# K104.net
KiCad netlist of a schematic drawn in EAGLE
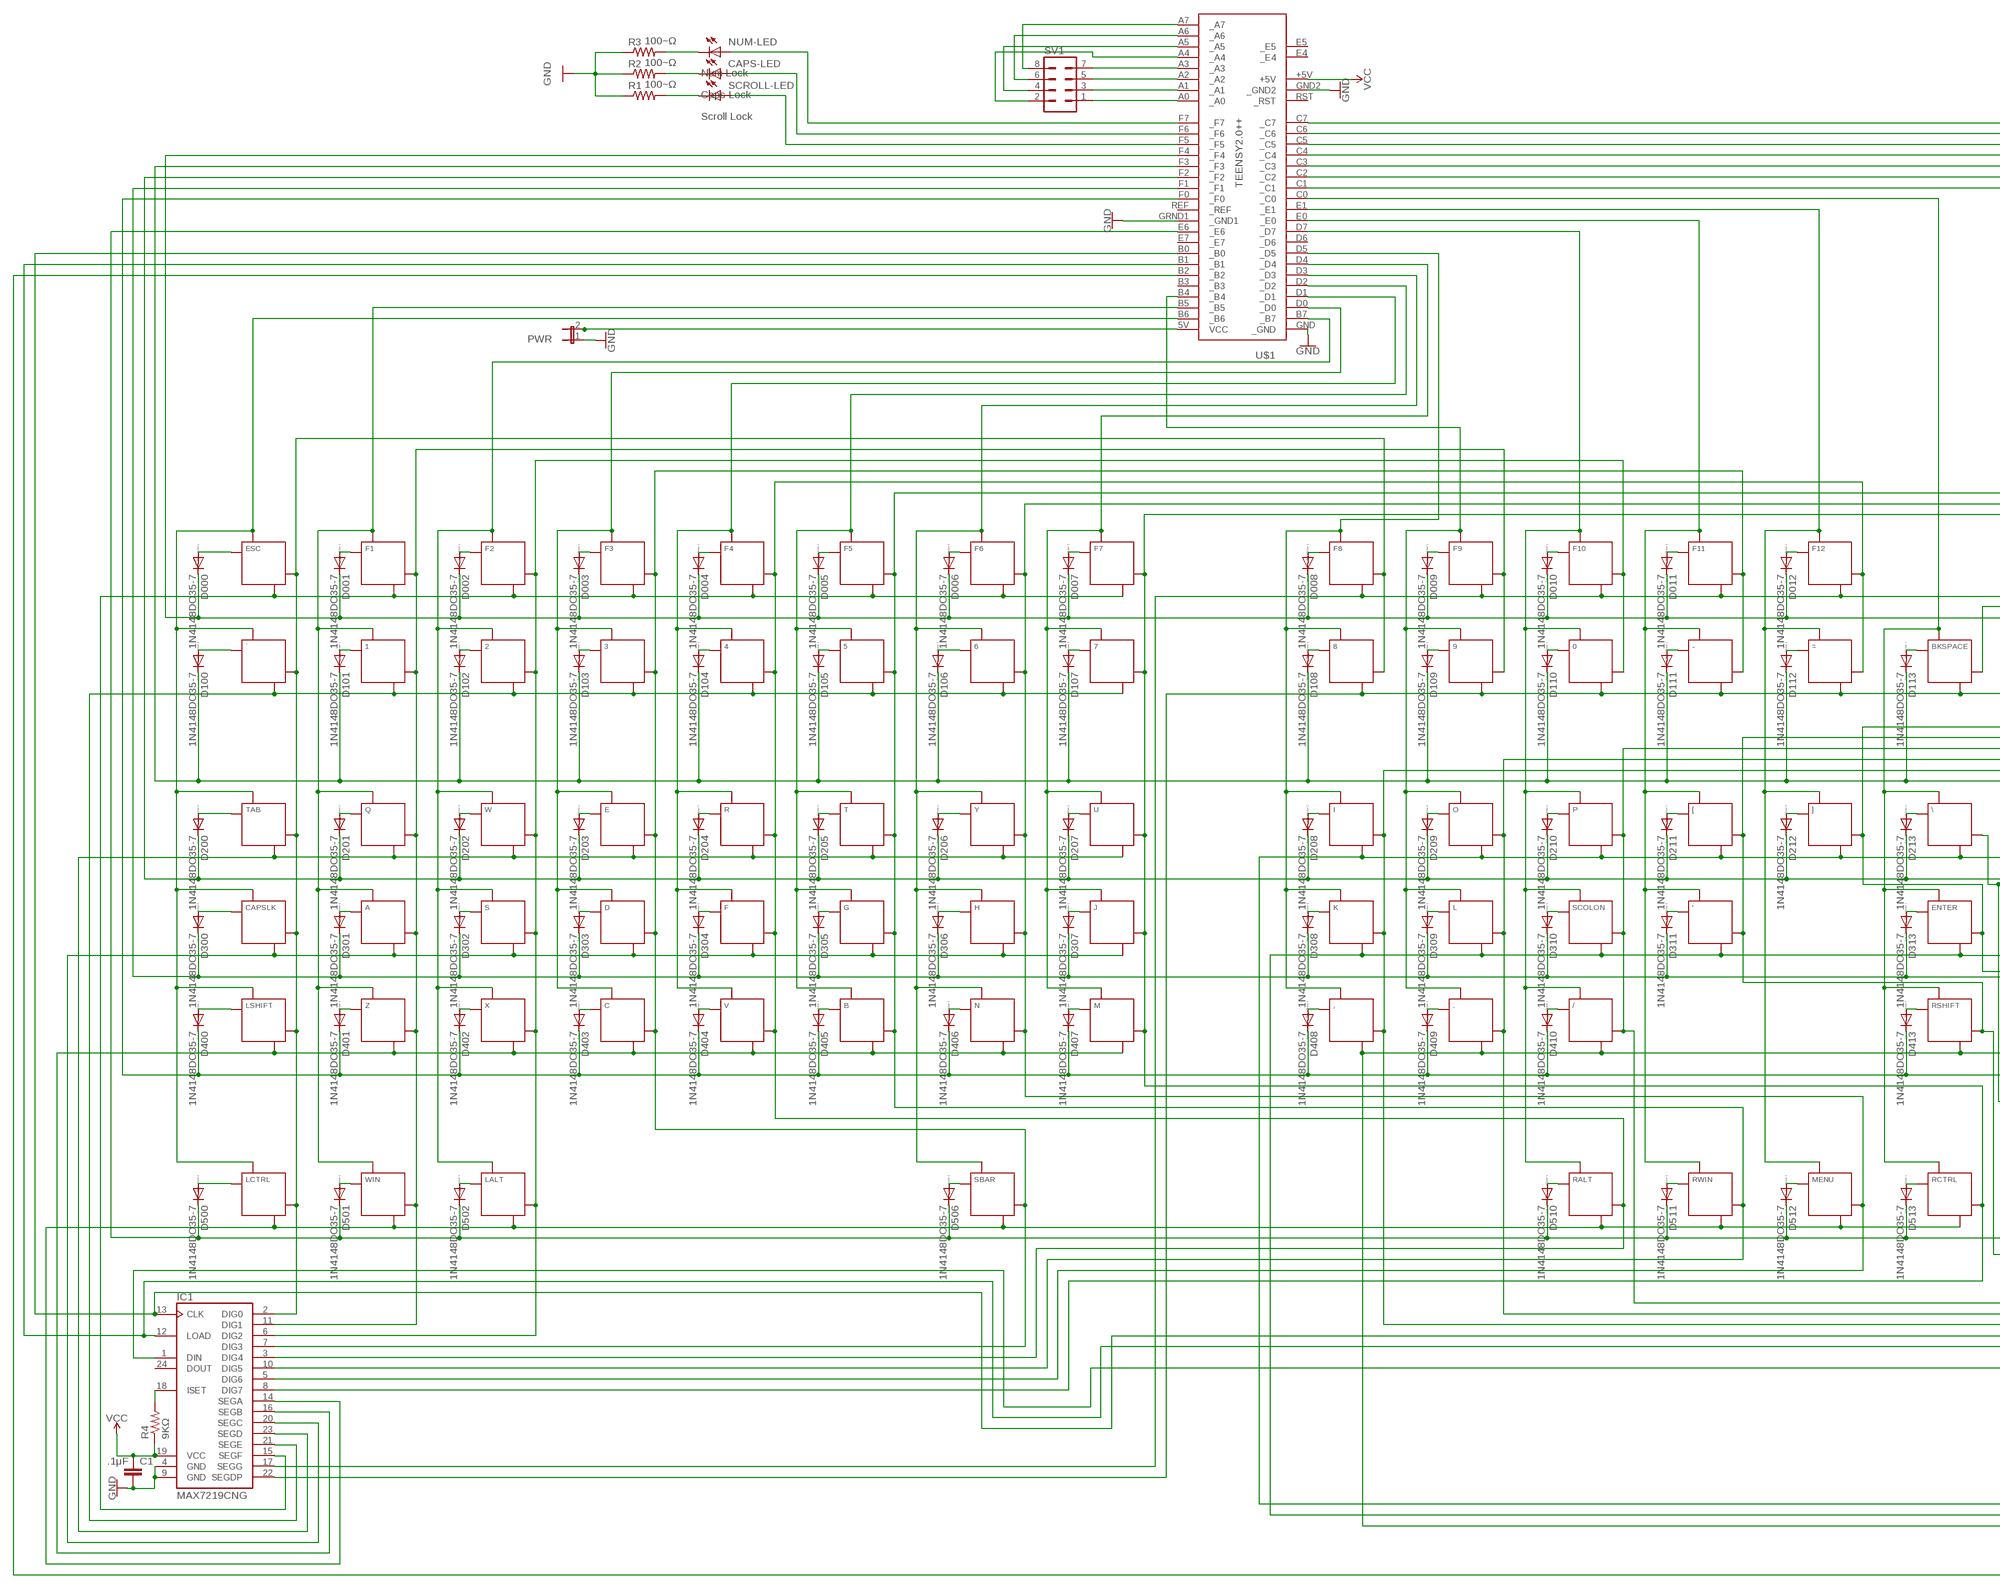
[diagram p0: schematic, sheet 1, part 1 of 2]
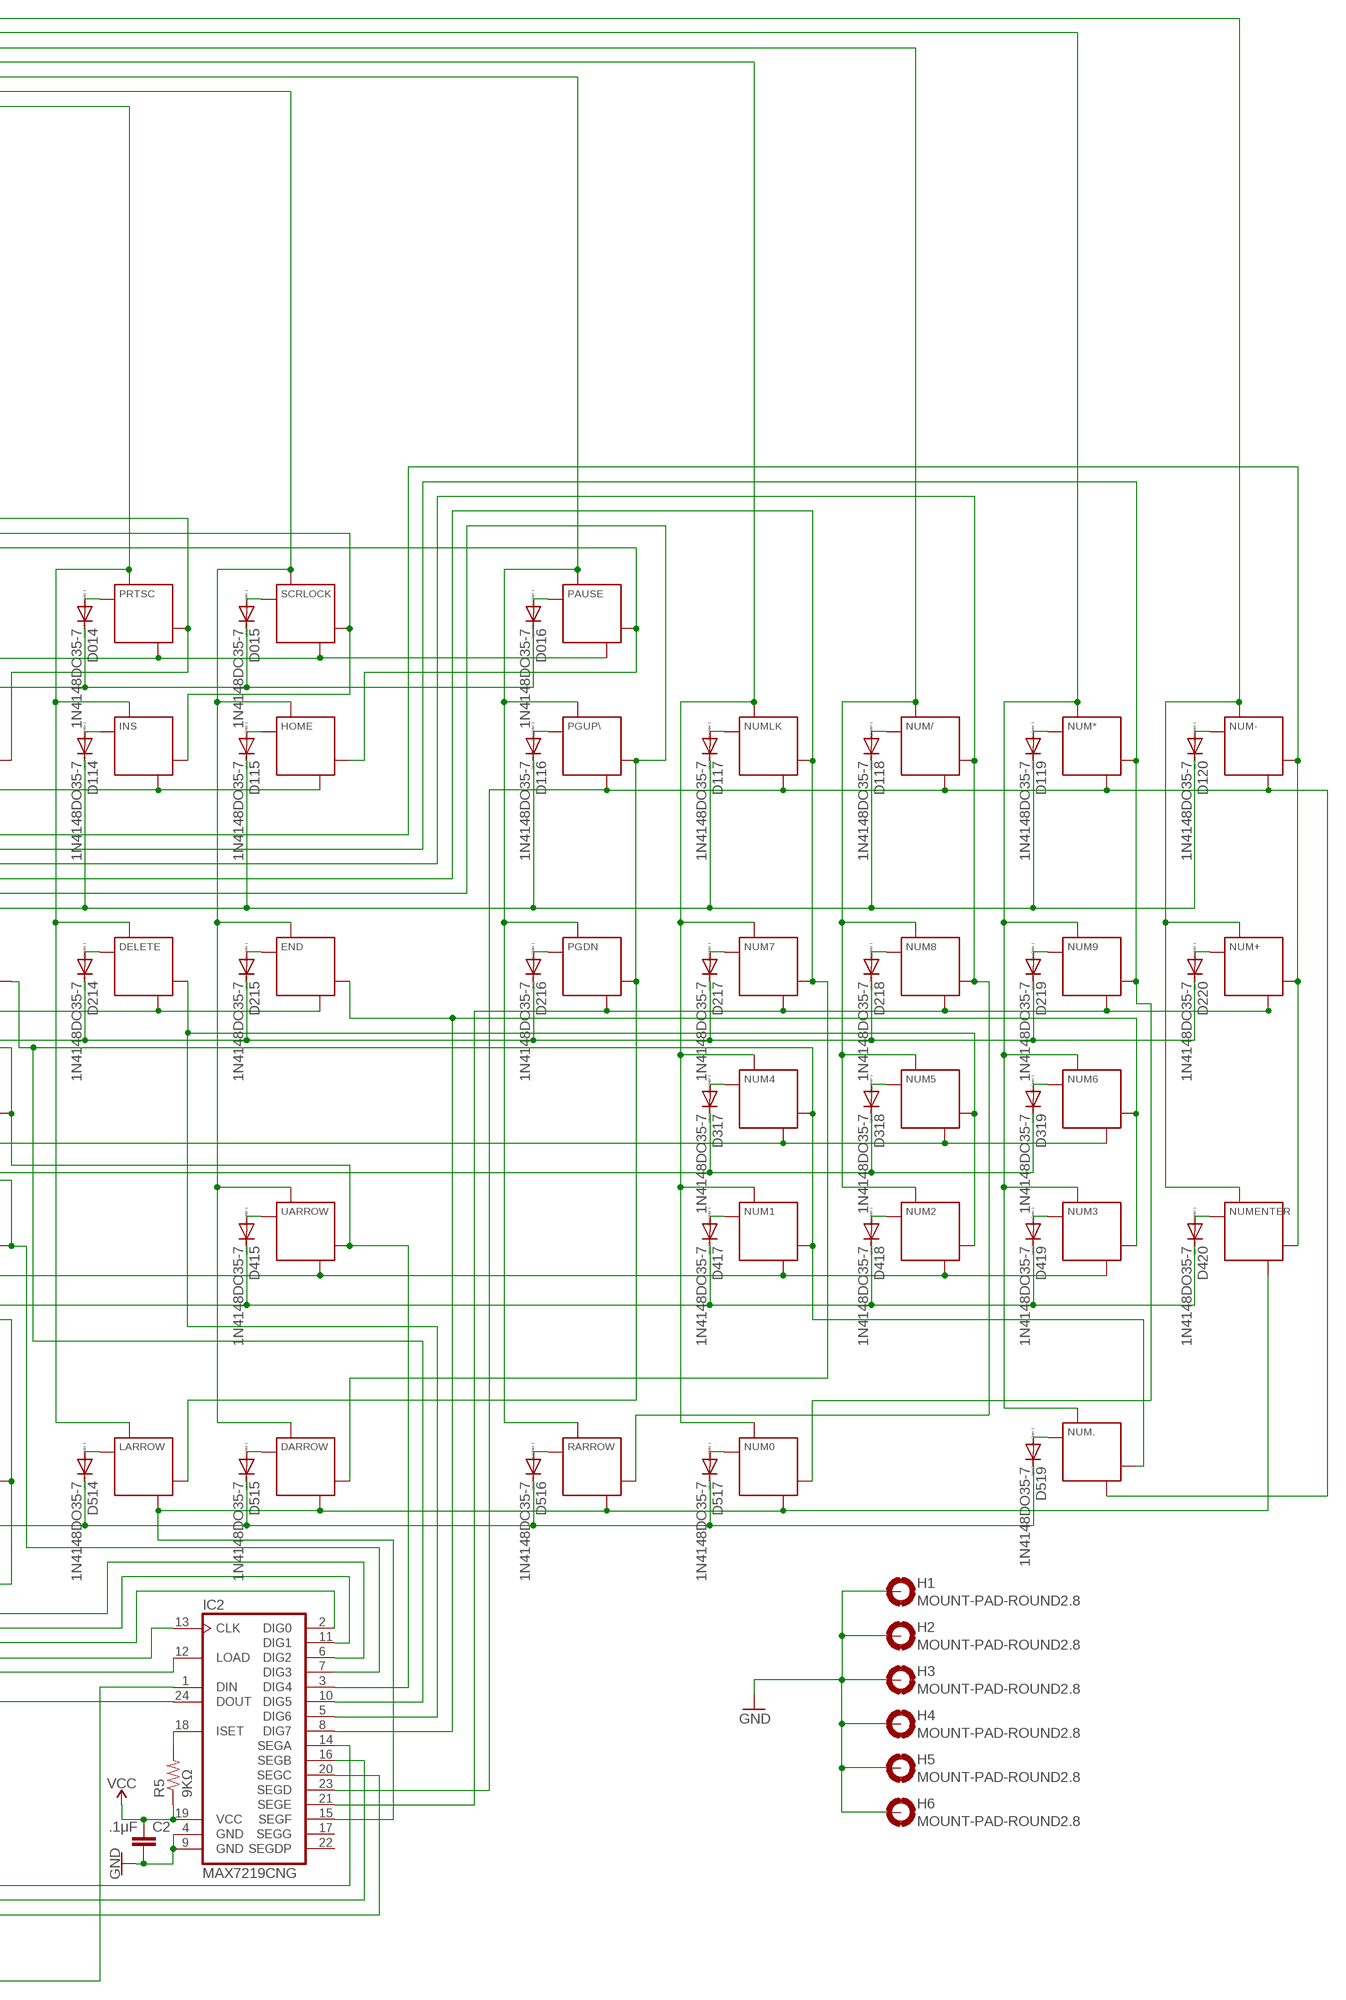
[diagram p1: schematic, sheet 1, part 2 of 2]

(export (version "E")
  (design (tool "Eeschema 10.0.6"))
  (components
    (comp (ref "'")
      (value "KEYSWITCH-LED-MX-1U-LED")
      (footprint "eagle-import:MX-1U-LED")
      (libsource (lib "eagle-import") (part "KEYSWITCH-LED-MX-1U-LED"))
    )
    (comp (ref ",")
      (value "KEYSWITCH-LED-MX-1U-LED")
      (footprint "eagle-import:MX-1U-LED")
      (libsource (lib "eagle-import") (part "KEYSWITCH-LED-MX-1U-LED"))
    )
    (comp (ref "-")
      (value "KEYSWITCH-LED-MX-1U-LED")
      (footprint "eagle-import:MX-1U-LED")
      (libsource (lib "eagle-import") (part "KEYSWITCH-LED-MX-1U-LED"))
    )
    (comp (ref ".")
      (value "KEYSWITCH-LED-MX-1U-LED")
      (footprint "eagle-import:MX-1U-LED")
      (libsource (lib "eagle-import") (part "KEYSWITCH-LED-MX-1U-LED"))
    )
    (comp (ref "/")
      (value "KEYSWITCH-LED-MX-1U-LED")
      (footprint "eagle-import:MX-1U-LED")
      (libsource (lib "eagle-import") (part "KEYSWITCH-LED-MX-1U-LED"))
    )
    (comp (ref "0")
      (value "KEYSWITCH-LED-MX-1U-LED")
      (footprint "eagle-import:MX-1U-LED")
      (libsource (lib "eagle-import") (part "KEYSWITCH-LED-MX-1U-LED"))
    )
    (comp (ref "1")
      (value "KEYSWITCH-LED-MX-1U-LED")
      (footprint "eagle-import:MX-1U-LED")
      (libsource (lib "eagle-import") (part "KEYSWITCH-LED-MX-1U-LED"))
    )
    (comp (ref "2")
      (value "KEYSWITCH-LED-MX-1U-LED")
      (footprint "eagle-import:MX-1U-LED")
      (libsource (lib "eagle-import") (part "KEYSWITCH-LED-MX-1U-LED"))
    )
    (comp (ref "3")
      (value "KEYSWITCH-LED-MX-1U-LED")
      (footprint "eagle-import:MX-1U-LED")
      (libsource (lib "eagle-import") (part "KEYSWITCH-LED-MX-1U-LED"))
    )
    (comp (ref "4")
      (value "KEYSWITCH-LED-MX-1U-LED")
      (footprint "eagle-import:MX-1U-LED")
      (libsource (lib "eagle-import") (part "KEYSWITCH-LED-MX-1U-LED"))
    )
    (comp (ref "5")
      (value "KEYSWITCH-LED-MX-1U-LED")
      (footprint "eagle-import:MX-1U-LED")
      (libsource (lib "eagle-import") (part "KEYSWITCH-LED-MX-1U-LED"))
    )
    (comp (ref "6")
      (value "KEYSWITCH-LED-MX-1U-LED")
      (footprint "eagle-import:MX-1U-LED")
      (libsource (lib "eagle-import") (part "KEYSWITCH-LED-MX-1U-LED"))
    )
    (comp (ref "7")
      (value "KEYSWITCH-LED-MX-1U-LED")
      (footprint "eagle-import:MX-1U-LED")
      (libsource (lib "eagle-import") (part "KEYSWITCH-LED-MX-1U-LED"))
    )
    (comp (ref "8")
      (value "KEYSWITCH-LED-MX-1U-LED")
      (footprint "eagle-import:MX-1U-LED")
      (libsource (lib "eagle-import") (part "KEYSWITCH-LED-MX-1U-LED"))
    )
    (comp (ref "9")
      (value "KEYSWITCH-LED-MX-1U-LED")
      (footprint "eagle-import:MX-1U-LED")
      (libsource (lib "eagle-import") (part "KEYSWITCH-LED-MX-1U-LED"))
    )
    (comp (ref "=")
      (value "KEYSWITCH-LED-MX-1U-LED")
      (footprint "eagle-import:MX-1U-LED")
      (libsource (lib "eagle-import") (part "KEYSWITCH-LED-MX-1U-LED"))
    )
    (comp (ref "A")
      (value "KEYSWITCH-LED-MX-1U-LED")
      (footprint "eagle-import:MX-1U-LED")
      (libsource (lib "eagle-import") (part "KEYSWITCH-LED-MX-1U-LED"))
    )
    (comp (ref "B")
      (value "KEYSWITCH-LED-MX-1U-LED")
      (footprint "eagle-import:MX-1U-LED")
      (libsource (lib "eagle-import") (part "KEYSWITCH-LED-MX-1U-LED"))
    )
    (comp (ref "BKSPACE")
      (value "KEYSWITCH-LED-MX-2U-LED")
      (footprint "eagle-import:MX-2U-LED")
      (libsource (lib "eagle-import") (part "KEYSWITCH-LED-MX-2U-LED"))
    )
    (comp (ref "C")
      (value "KEYSWITCH-LED-MX-1U-LED")
      (footprint "eagle-import:MX-1U-LED")
      (libsource (lib "eagle-import") (part "KEYSWITCH-LED-MX-1U-LED"))
    )
    (comp (ref "C1")
      (value ".1μF")
      (footprint "eagle-import:C025-024X044")
      (libsource (lib "eagle-import") (part "C-EU025-024X044"))
    )
    (comp (ref "C2")
      (value ".1μF")
      (footprint "eagle-import:C025-024X044")
      (libsource (lib "eagle-import") (part "C-EU025-024X044"))
    )
    (comp (ref "CAPS-LED")
      (value "Caps Lock")
      (footprint "eagle-import:LED3MM")
      (libsource (lib "eagle-import") (part "LED3MM"))
    )
    (comp (ref "CAPSLK")
      (value "KEYSWITCH-LED-MX-1U-LED")
      (footprint "eagle-import:MX-1U-LED")
      (libsource (lib "eagle-import") (part "KEYSWITCH-LED-MX-1U-LED"))
    )
    (comp (ref "D")
      (value "KEYSWITCH-LED-MX-1U-LED")
      (footprint "eagle-import:MX-1U-LED")
      (libsource (lib "eagle-import") (part "KEYSWITCH-LED-MX-1U-LED"))
    )
    (comp (ref "D000")
      (value "1N4148DO35-7")
      (footprint "eagle-import:DO35-7")
      (libsource (lib "eagle-import") (part "1N4148DO35-7"))
    )
    (comp (ref "D001")
      (value "1N4148DO35-7")
      (footprint "eagle-import:DO35-7")
      (libsource (lib "eagle-import") (part "1N4148DO35-7"))
    )
    (comp (ref "D002")
      (value "1N4148DO35-7")
      (footprint "eagle-import:DO35-7")
      (libsource (lib "eagle-import") (part "1N4148DO35-7"))
    )
    (comp (ref "D003")
      (value "1N4148DO35-7")
      (footprint "eagle-import:DO35-7")
      (libsource (lib "eagle-import") (part "1N4148DO35-7"))
    )
    (comp (ref "D004")
      (value "1N4148DO35-7")
      (footprint "eagle-import:DO35-7")
      (libsource (lib "eagle-import") (part "1N4148DO35-7"))
    )
    (comp (ref "D005")
      (value "1N4148DO35-7")
      (footprint "eagle-import:DO35-7")
      (libsource (lib "eagle-import") (part "1N4148DO35-7"))
    )
    (comp (ref "D006")
      (value "1N4148DO35-7")
      (footprint "eagle-import:DO35-7")
      (libsource (lib "eagle-import") (part "1N4148DO35-7"))
    )
    (comp (ref "D007")
      (value "1N4148DO35-7")
      (footprint "eagle-import:DO35-7")
      (libsource (lib "eagle-import") (part "1N4148DO35-7"))
    )
    (comp (ref "D008")
      (value "1N4148DO35-7")
      (footprint "eagle-import:DO35-7")
      (libsource (lib "eagle-import") (part "1N4148DO35-7"))
    )
    (comp (ref "D009")
      (value "1N4148DO35-7")
      (footprint "eagle-import:DO35-7")
      (libsource (lib "eagle-import") (part "1N4148DO35-7"))
    )
    (comp (ref "D010")
      (value "1N4148DO35-7")
      (footprint "eagle-import:DO35-7")
      (libsource (lib "eagle-import") (part "1N4148DO35-7"))
    )
    (comp (ref "D011")
      (value "1N4148DO35-7")
      (footprint "eagle-import:DO35-7")
      (libsource (lib "eagle-import") (part "1N4148DO35-7"))
    )
    (comp (ref "D012")
      (value "1N4148DO35-7")
      (footprint "eagle-import:DO35-7")
      (libsource (lib "eagle-import") (part "1N4148DO35-7"))
    )
    (comp (ref "D014")
      (value "1N4148DO35-7")
      (footprint "eagle-import:DO35-7")
      (libsource (lib "eagle-import") (part "1N4148DO35-7"))
    )
    (comp (ref "D015")
      (value "1N4148DO35-7")
      (footprint "eagle-import:DO35-7")
      (libsource (lib "eagle-import") (part "1N4148DO35-7"))
    )
    (comp (ref "D016")
      (value "1N4148DO35-7")
      (footprint "eagle-import:DO35-7")
      (libsource (lib "eagle-import") (part "1N4148DO35-7"))
    )
    (comp (ref "D100")
      (value "1N4148DO35-7")
      (footprint "eagle-import:DO35-7")
      (libsource (lib "eagle-import") (part "1N4148DO35-7"))
    )
    (comp (ref "D101")
      (value "1N4148DO35-7")
      (footprint "eagle-import:DO35-7")
      (libsource (lib "eagle-import") (part "1N4148DO35-7"))
    )
    (comp (ref "D102")
      (value "1N4148DO35-7")
      (footprint "eagle-import:DO35-7")
      (libsource (lib "eagle-import") (part "1N4148DO35-7"))
    )
    (comp (ref "D103")
      (value "1N4148DO35-7")
      (footprint "eagle-import:DO35-7")
      (libsource (lib "eagle-import") (part "1N4148DO35-7"))
    )
    (comp (ref "D104")
      (value "1N4148DO35-7")
      (footprint "eagle-import:DO35-7")
      (libsource (lib "eagle-import") (part "1N4148DO35-7"))
    )
    (comp (ref "D105")
      (value "1N4148DO35-7")
      (footprint "eagle-import:DO35-7")
      (libsource (lib "eagle-import") (part "1N4148DO35-7"))
    )
    (comp (ref "D106")
      (value "1N4148DO35-7")
      (footprint "eagle-import:DO35-7")
      (libsource (lib "eagle-import") (part "1N4148DO35-7"))
    )
    (comp (ref "D107")
      (value "1N4148DO35-7")
      (footprint "eagle-import:DO35-7")
      (libsource (lib "eagle-import") (part "1N4148DO35-7"))
    )
    (comp (ref "D108")
      (value "1N4148DO35-7")
      (footprint "eagle-import:DO35-7")
      (libsource (lib "eagle-import") (part "1N4148DO35-7"))
    )
    (comp (ref "D109")
      (value "1N4148DO35-7")
      (footprint "eagle-import:DO35-7")
      (libsource (lib "eagle-import") (part "1N4148DO35-7"))
    )
    (comp (ref "D110")
      (value "1N4148DO35-7")
      (footprint "eagle-import:DO35-7")
      (libsource (lib "eagle-import") (part "1N4148DO35-7"))
    )
    (comp (ref "D111")
      (value "1N4148DO35-7")
      (footprint "eagle-import:DO35-7")
      (libsource (lib "eagle-import") (part "1N4148DO35-7"))
    )
    (comp (ref "D112")
      (value "1N4148DO35-7")
      (footprint "eagle-import:DO35-7")
      (libsource (lib "eagle-import") (part "1N4148DO35-7"))
    )
    (comp (ref "D113")
      (value "1N4148DO35-7")
      (footprint "eagle-import:DO35-7")
      (libsource (lib "eagle-import") (part "1N4148DO35-7"))
    )
    (comp (ref "D114")
      (value "1N4148DO35-7")
      (footprint "eagle-import:DO35-7")
      (libsource (lib "eagle-import") (part "1N4148DO35-7"))
    )
    (comp (ref "D115")
      (value "1N4148DO35-7")
      (footprint "eagle-import:DO35-7")
      (libsource (lib "eagle-import") (part "1N4148DO35-7"))
    )
    (comp (ref "D116")
      (value "1N4148DO35-7")
      (footprint "eagle-import:DO35-7")
      (libsource (lib "eagle-import") (part "1N4148DO35-7"))
    )
    (comp (ref "D117")
      (value "1N4148DO35-7")
      (footprint "eagle-import:DO35-7")
      (libsource (lib "eagle-import") (part "1N4148DO35-7"))
    )
    (comp (ref "D118")
      (value "1N4148DO35-7")
      (footprint "eagle-import:DO35-7")
      (libsource (lib "eagle-import") (part "1N4148DO35-7"))
    )
    (comp (ref "D119")
      (value "1N4148DO35-7")
      (footprint "eagle-import:DO35-7")
      (libsource (lib "eagle-import") (part "1N4148DO35-7"))
    )
    (comp (ref "D120")
      (value "1N4148DO35-7")
      (footprint "eagle-import:DO35-7")
      (libsource (lib "eagle-import") (part "1N4148DO35-7"))
    )
    (comp (ref "D200")
      (value "1N4148DO35-7")
      (footprint "eagle-import:DO35-7")
      (libsource (lib "eagle-import") (part "1N4148DO35-7"))
    )
    (comp (ref "D201")
      (value "1N4148DO35-7")
      (footprint "eagle-import:DO35-7")
      (libsource (lib "eagle-import") (part "1N4148DO35-7"))
    )
    (comp (ref "D202")
      (value "1N4148DO35-7")
      (footprint "eagle-import:DO35-7")
      (libsource (lib "eagle-import") (part "1N4148DO35-7"))
    )
    (comp (ref "D203")
      (value "1N4148DO35-7")
      (footprint "eagle-import:DO35-7")
      (libsource (lib "eagle-import") (part "1N4148DO35-7"))
    )
    (comp (ref "D204")
      (value "1N4148DO35-7")
      (footprint "eagle-import:DO35-7")
      (libsource (lib "eagle-import") (part "1N4148DO35-7"))
    )
    (comp (ref "D205")
      (value "1N4148DO35-7")
      (footprint "eagle-import:DO35-7")
      (libsource (lib "eagle-import") (part "1N4148DO35-7"))
    )
    (comp (ref "D206")
      (value "1N4148DO35-7")
      (footprint "eagle-import:DO35-7")
      (libsource (lib "eagle-import") (part "1N4148DO35-7"))
    )
    (comp (ref "D207")
      (value "1N4148DO35-7")
      (footprint "eagle-import:DO35-7")
      (libsource (lib "eagle-import") (part "1N4148DO35-7"))
    )
    (comp (ref "D208")
      (value "1N4148DO35-7")
      (footprint "eagle-import:DO35-7")
      (libsource (lib "eagle-import") (part "1N4148DO35-7"))
    )
    (comp (ref "D209")
      (value "1N4148DO35-7")
      (footprint "eagle-import:DO35-7")
      (libsource (lib "eagle-import") (part "1N4148DO35-7"))
    )
    (comp (ref "D210")
      (value "1N4148DO35-7")
      (footprint "eagle-import:DO35-7")
      (libsource (lib "eagle-import") (part "1N4148DO35-7"))
    )
    (comp (ref "D211")
      (value "1N4148DO35-7")
      (footprint "eagle-import:DO35-7")
      (libsource (lib "eagle-import") (part "1N4148DO35-7"))
    )
    (comp (ref "D212")
      (value "1N4148DO35-7")
      (footprint "eagle-import:DO35-7")
      (libsource (lib "eagle-import") (part "1N4148DO35-7"))
    )
    (comp (ref "D213")
      (value "1N4148DO35-7")
      (footprint "eagle-import:DO35-7")
      (libsource (lib "eagle-import") (part "1N4148DO35-7"))
    )
    (comp (ref "D214")
      (value "1N4148DO35-7")
      (footprint "eagle-import:DO35-7")
      (libsource (lib "eagle-import") (part "1N4148DO35-7"))
    )
    (comp (ref "D215")
      (value "1N4148DO35-7")
      (footprint "eagle-import:DO35-7")
      (libsource (lib "eagle-import") (part "1N4148DO35-7"))
    )
    (comp (ref "D216")
      (value "1N4148DO35-7")
      (footprint "eagle-import:DO35-7")
      (libsource (lib "eagle-import") (part "1N4148DO35-7"))
    )
    (comp (ref "D217")
      (value "1N4148DO35-7")
      (footprint "eagle-import:DO35-7")
      (libsource (lib "eagle-import") (part "1N4148DO35-7"))
    )
    (comp (ref "D218")
      (value "1N4148DO35-7")
      (footprint "eagle-import:DO35-7")
      (libsource (lib "eagle-import") (part "1N4148DO35-7"))
    )
    (comp (ref "D219")
      (value "1N4148DO35-7")
      (footprint "eagle-import:DO35-7")
      (libsource (lib "eagle-import") (part "1N4148DO35-7"))
    )
    (comp (ref "D220")
      (value "1N4148DO35-7")
      (footprint "eagle-import:DO35-7")
      (libsource (lib "eagle-import") (part "1N4148DO35-7"))
    )
    (comp (ref "D300")
      (value "1N4148DO35-7")
      (footprint "eagle-import:DO35-7")
      (libsource (lib "eagle-import") (part "1N4148DO35-7"))
    )
    (comp (ref "D301")
      (value "1N4148DO35-7")
      (footprint "eagle-import:DO35-7")
      (libsource (lib "eagle-import") (part "1N4148DO35-7"))
    )
    (comp (ref "D302")
      (value "1N4148DO35-7")
      (footprint "eagle-import:DO35-7")
      (libsource (lib "eagle-import") (part "1N4148DO35-7"))
    )
    (comp (ref "D303")
      (value "1N4148DO35-7")
      (footprint "eagle-import:DO35-7")
      (libsource (lib "eagle-import") (part "1N4148DO35-7"))
    )
    (comp (ref "D304")
      (value "1N4148DO35-7")
      (footprint "eagle-import:DO35-7")
      (libsource (lib "eagle-import") (part "1N4148DO35-7"))
    )
    (comp (ref "D305")
      (value "1N4148DO35-7")
      (footprint "eagle-import:DO35-7")
      (libsource (lib "eagle-import") (part "1N4148DO35-7"))
    )
    (comp (ref "D306")
      (value "1N4148DO35-7")
      (footprint "eagle-import:DO35-7")
      (libsource (lib "eagle-import") (part "1N4148DO35-7"))
    )
    (comp (ref "D307")
      (value "1N4148DO35-7")
      (footprint "eagle-import:DO35-7")
      (libsource (lib "eagle-import") (part "1N4148DO35-7"))
    )
    (comp (ref "D308")
      (value "1N4148DO35-7")
      (footprint "eagle-import:DO35-7")
      (libsource (lib "eagle-import") (part "1N4148DO35-7"))
    )
    (comp (ref "D309")
      (value "1N4148DO35-7")
      (footprint "eagle-import:DO35-7")
      (libsource (lib "eagle-import") (part "1N4148DO35-7"))
    )
    (comp (ref "D310")
      (value "1N4148DO35-7")
      (footprint "eagle-import:DO35-7")
      (libsource (lib "eagle-import") (part "1N4148DO35-7"))
    )
    (comp (ref "D311")
      (value "1N4148DO35-7")
      (footprint "eagle-import:DO35-7")
      (libsource (lib "eagle-import") (part "1N4148DO35-7"))
    )
    (comp (ref "D313")
      (value "1N4148DO35-7")
      (footprint "eagle-import:DO35-7")
      (libsource (lib "eagle-import") (part "1N4148DO35-7"))
    )
    (comp (ref "D317")
      (value "1N4148DO35-7")
      (footprint "eagle-import:DO35-7")
      (libsource (lib "eagle-import") (part "1N4148DO35-7"))
    )
    (comp (ref "D318")
      (value "1N4148DO35-7")
      (footprint "eagle-import:DO35-7")
      (libsource (lib "eagle-import") (part "1N4148DO35-7"))
    )
    (comp (ref "D319")
      (value "1N4148DO35-7")
      (footprint "eagle-import:DO35-7")
      (libsource (lib "eagle-import") (part "1N4148DO35-7"))
    )
    (comp (ref "D400")
      (value "1N4148DO35-7")
      (footprint "eagle-import:DO35-7")
      (libsource (lib "eagle-import") (part "1N4148DO35-7"))
    )
    (comp (ref "D401")
      (value "1N4148DO35-7")
      (footprint "eagle-import:DO35-7")
      (libsource (lib "eagle-import") (part "1N4148DO35-7"))
    )
    (comp (ref "D402")
      (value "1N4148DO35-7")
      (footprint "eagle-import:DO35-7")
      (libsource (lib "eagle-import") (part "1N4148DO35-7"))
    )
    (comp (ref "D403")
      (value "1N4148DO35-7")
      (footprint "eagle-import:DO35-7")
      (libsource (lib "eagle-import") (part "1N4148DO35-7"))
    )
    (comp (ref "D404")
      (value "1N4148DO35-7")
      (footprint "eagle-import:DO35-7")
      (libsource (lib "eagle-import") (part "1N4148DO35-7"))
    )
    (comp (ref "D405")
      (value "1N4148DO35-7")
      (footprint "eagle-import:DO35-7")
      (libsource (lib "eagle-import") (part "1N4148DO35-7"))
    )
    (comp (ref "D406")
      (value "1N4148DO35-7")
      (footprint "eagle-import:DO35-7")
      (libsource (lib "eagle-import") (part "1N4148DO35-7"))
    )
    (comp (ref "D407")
      (value "1N4148DO35-7")
      (footprint "eagle-import:DO35-7")
      (libsource (lib "eagle-import") (part "1N4148DO35-7"))
    )
    (comp (ref "D408")
      (value "1N4148DO35-7")
      (footprint "eagle-import:DO35-7")
      (libsource (lib "eagle-import") (part "1N4148DO35-7"))
    )
    (comp (ref "D409")
      (value "1N4148DO35-7")
      (footprint "eagle-import:DO35-7")
      (libsource (lib "eagle-import") (part "1N4148DO35-7"))
    )
    (comp (ref "D410")
      (value "1N4148DO35-7")
      (footprint "eagle-import:DO35-7")
      (libsource (lib "eagle-import") (part "1N4148DO35-7"))
    )
    (comp (ref "D413")
      (value "1N4148DO35-7")
      (footprint "eagle-import:DO35-7")
      (libsource (lib "eagle-import") (part "1N4148DO35-7"))
    )
    (comp (ref "D415")
      (value "1N4148DO35-7")
      (footprint "eagle-import:DO35-7")
      (libsource (lib "eagle-import") (part "1N4148DO35-7"))
    )
    (comp (ref "D417")
      (value "1N4148DO35-7")
      (footprint "eagle-import:DO35-7")
      (libsource (lib "eagle-import") (part "1N4148DO35-7"))
    )
    (comp (ref "D418")
      (value "1N4148DO35-7")
      (footprint "eagle-import:DO35-7")
      (libsource (lib "eagle-import") (part "1N4148DO35-7"))
    )
    (comp (ref "D419")
      (value "1N4148DO35-7")
      (footprint "eagle-import:DO35-7")
      (libsource (lib "eagle-import") (part "1N4148DO35-7"))
    )
    (comp (ref "D420")
      (value "1N4148DO35-7")
      (footprint "eagle-import:DO35-7")
      (libsource (lib "eagle-import") (part "1N4148DO35-7"))
    )
    (comp (ref "D500")
      (value "1N4148DO35-7")
      (footprint "eagle-import:DO35-7")
      (libsource (lib "eagle-import") (part "1N4148DO35-7"))
    )
    (comp (ref "D501")
      (value "1N4148DO35-7")
      (footprint "eagle-import:DO35-7")
      (libsource (lib "eagle-import") (part "1N4148DO35-7"))
    )
    (comp (ref "D502")
      (value "1N4148DO35-7")
      (footprint "eagle-import:DO35-7")
      (libsource (lib "eagle-import") (part "1N4148DO35-7"))
    )
    (comp (ref "D506")
      (value "1N4148DO35-7")
      (footprint "eagle-import:DO35-7")
      (libsource (lib "eagle-import") (part "1N4148DO35-7"))
    )
    (comp (ref "D510")
      (value "1N4148DO35-7")
      (footprint "eagle-import:DO35-7")
      (libsource (lib "eagle-import") (part "1N4148DO35-7"))
    )
    (comp (ref "D511")
      (value "1N4148DO35-7")
      (footprint "eagle-import:DO35-7")
      (libsource (lib "eagle-import") (part "1N4148DO35-7"))
    )
    (comp (ref "D512")
      (value "1N4148DO35-7")
      (footprint "eagle-import:DO35-7")
      (libsource (lib "eagle-import") (part "1N4148DO35-7"))
    )
    (comp (ref "D513")
      (value "1N4148DO35-7")
      (footprint "eagle-import:DO35-7")
      (libsource (lib "eagle-import") (part "1N4148DO35-7"))
    )
    (comp (ref "D514")
      (value "1N4148DO35-7")
      (footprint "eagle-import:DO35-7")
      (libsource (lib "eagle-import") (part "1N4148DO35-7"))
    )
    (comp (ref "D515")
      (value "1N4148DO35-7")
      (footprint "eagle-import:DO35-7")
      (libsource (lib "eagle-import") (part "1N4148DO35-7"))
    )
    (comp (ref "D516")
      (value "1N4148DO35-7")
      (footprint "eagle-import:DO35-7")
      (libsource (lib "eagle-import") (part "1N4148DO35-7"))
    )
    (comp (ref "D517")
      (value "1N4148DO35-7")
      (footprint "eagle-import:DO35-7")
      (libsource (lib "eagle-import") (part "1N4148DO35-7"))
    )
    (comp (ref "D519")
      (value "1N4148DO35-7")
      (footprint "eagle-import:DO35-7")
      (libsource (lib "eagle-import") (part "1N4148DO35-7"))
    )
    (comp (ref "DARROW")
      (value "KEYSWITCH-LED-MX-1U-LED")
      (footprint "eagle-import:MX-1U-LED")
      (libsource (lib "eagle-import") (part "KEYSWITCH-LED-MX-1U-LED"))
    )
    (comp (ref "DELETE")
      (value "KEYSWITCH-LED-MX-1U-LED")
      (footprint "eagle-import:MX-1U-LED")
      (libsource (lib "eagle-import") (part "KEYSWITCH-LED-MX-1U-LED"))
    )
    (comp (ref "E")
      (value "KEYSWITCH-LED-MX-1U-LED")
      (footprint "eagle-import:MX-1U-LED")
      (libsource (lib "eagle-import") (part "KEYSWITCH-LED-MX-1U-LED"))
    )
    (comp (ref "END")
      (value "KEYSWITCH-LED-MX-1U-LED")
      (footprint "eagle-import:MX-1U-LED")
      (libsource (lib "eagle-import") (part "KEYSWITCH-LED-MX-1U-LED"))
    )
    (comp (ref "ENTER")
      (value "KEYSWITCH-LED-MX-2U-LED")
      (footprint "eagle-import:MX-2U-LED")
      (libsource (lib "eagle-import") (part "KEYSWITCH-LED-MX-2U-LED"))
    )
    (comp (ref "ESC")
      (value "S001")
      (footprint "eagle-import:MX-1U-LED")
      (libsource (lib "eagle-import") (part "KEYSWITCH-LED-MX-1U-LED"))
    )
    (comp (ref "F")
      (value "KEYSWITCH-LED-MX-1U-LED")
      (footprint "eagle-import:MX-1U-LED")
      (libsource (lib "eagle-import") (part "KEYSWITCH-LED-MX-1U-LED"))
    )
    (comp (ref "F1")
      (value "KEYSWITCH-LED-MX-1U-LED")
      (footprint "eagle-import:MX-1U-LED")
      (libsource (lib "eagle-import") (part "KEYSWITCH-LED-MX-1U-LED"))
    )
    (comp (ref "F2")
      (value "KEYSWITCH-LED-MX-1U-LED")
      (footprint "eagle-import:MX-1U-LED")
      (libsource (lib "eagle-import") (part "KEYSWITCH-LED-MX-1U-LED"))
    )
    (comp (ref "F3")
      (value "KEYSWITCH-LED-MX-1U-LED")
      (footprint "eagle-import:MX-1U-LED")
      (libsource (lib "eagle-import") (part "KEYSWITCH-LED-MX-1U-LED"))
    )
    (comp (ref "F4")
      (value "KEYSWITCH-LED-MX-1U-LED")
      (footprint "eagle-import:MX-1U-LED")
      (libsource (lib "eagle-import") (part "KEYSWITCH-LED-MX-1U-LED"))
    )
    (comp (ref "F5")
      (value "KEYSWITCH-LED-MX-1U-LED")
      (footprint "eagle-import:MX-1U-LED")
      (libsource (lib "eagle-import") (part "KEYSWITCH-LED-MX-1U-LED"))
    )
    (comp (ref "F6")
      (value "KEYSWITCH-LED-MX-1U-LED")
      (footprint "eagle-import:MX-1U-LED")
      (libsource (lib "eagle-import") (part "KEYSWITCH-LED-MX-1U-LED"))
    )
    (comp (ref "F7")
      (value "KEYSWITCH-LED-MX-1U-LED")
      (footprint "eagle-import:MX-1U-LED")
      (libsource (lib "eagle-import") (part "KEYSWITCH-LED-MX-1U-LED"))
    )
    (comp (ref "F8")
      (value "KEYSWITCH-LED-MX-1U-LED")
      (footprint "eagle-import:MX-1U-LED")
      (libsource (lib "eagle-import") (part "KEYSWITCH-LED-MX-1U-LED"))
    )
    (comp (ref "F9")
      (value "KEYSWITCH-LED-MX-1U-LED")
      (footprint "eagle-import:MX-1U-LED")
      (libsource (lib "eagle-import") (part "KEYSWITCH-LED-MX-1U-LED"))
    )
    (comp (ref "F10")
      (value "KEYSWITCH-LED-MX-1U-LED")
      (footprint "eagle-import:MX-1U-LED")
      (libsource (lib "eagle-import") (part "KEYSWITCH-LED-MX-1U-LED"))
    )
    (comp (ref "F11")
      (value "KEYSWITCH-LED-MX-1U-LED")
      (footprint "eagle-import:MX-1U-LED")
      (libsource (lib "eagle-import") (part "KEYSWITCH-LED-MX-1U-LED"))
    )
    (comp (ref "F12")
      (value "KEYSWITCH-LED-MX-1U-LED")
      (footprint "eagle-import:MX-1U-LED")
      (libsource (lib "eagle-import") (part "KEYSWITCH-LED-MX-1U-LED"))
    )
    (comp (ref "G")
      (value "KEYSWITCH-LED-MX-1U-LED")
      (footprint "eagle-import:MX-1U-LED")
      (libsource (lib "eagle-import") (part "KEYSWITCH-LED-MX-1U-LED"))
    )
    (comp (ref "H")
      (value "KEYSWITCH-LED-MX-1U-LED")
      (footprint "eagle-import:MX-1U-LED")
      (libsource (lib "eagle-import") (part "KEYSWITCH-LED-MX-1U-LED"))
    )
    (comp (ref "H1")
      (value "MOUNT-PAD-ROUND2.8")
      (footprint "eagle-import:2,8-PAD")
      (libsource (lib "eagle-import") (part "MOUNT-PAD-ROUND2.8"))
    )
    (comp (ref "H2")
      (value "MOUNT-PAD-ROUND2.8")
      (footprint "eagle-import:2,8-PAD")
      (libsource (lib "eagle-import") (part "MOUNT-PAD-ROUND2.8"))
    )
    (comp (ref "H3")
      (value "MOUNT-PAD-ROUND2.8")
      (footprint "eagle-import:2,8-PAD")
      (libsource (lib "eagle-import") (part "MOUNT-PAD-ROUND2.8"))
    )
    (comp (ref "H4")
      (value "MOUNT-PAD-ROUND2.8")
      (footprint "eagle-import:2,8-PAD")
      (libsource (lib "eagle-import") (part "MOUNT-PAD-ROUND2.8"))
    )
    (comp (ref "H5")
      (value "MOUNT-PAD-ROUND2.8")
      (footprint "eagle-import:2,8-PAD")
      (libsource (lib "eagle-import") (part "MOUNT-PAD-ROUND2.8"))
    )
    (comp (ref "H6")
      (value "MOUNT-PAD-ROUND2.8")
      (footprint "eagle-import:2,8-PAD")
      (libsource (lib "eagle-import") (part "MOUNT-PAD-ROUND2.8"))
    )
    (comp (ref "HOME")
      (value "KEYSWITCH-LED-MX-1U-LED")
      (footprint "eagle-import:MX-1U-LED")
      (libsource (lib "eagle-import") (part "KEYSWITCH-LED-MX-1U-LED"))
    )
    (comp (ref "I")
      (value "KEYSWITCH-LED-MX-1U-LED")
      (footprint "eagle-import:MX-1U-LED")
      (libsource (lib "eagle-import") (part "KEYSWITCH-LED-MX-1U-LED"))
    )
    (comp (ref "IC1")
      (value "MAX7219CNG")
      (footprint "eagle-import:DIL24-3")
      (fields (field (name "MF") "MAXIM"))
      (libsource (lib "eagle-import") (part "MAX7219CNG"))
    )
    (comp (ref "IC2")
      (value "MAX7219CNG")
      (footprint "eagle-import:DIL24-3")
      (fields (field (name "MF") "MAXIM"))
      (libsource (lib "eagle-import") (part "MAX7219CNG"))
    )
    (comp (ref "INS")
      (value "KEYSWITCH-LED-MX-1U-LED")
      (footprint "eagle-import:MX-1U-LED")
      (libsource (lib "eagle-import") (part "KEYSWITCH-LED-MX-1U-LED"))
    )
    (comp (ref "J")
      (value "KEYSWITCH-LED-MX-1U-LED")
      (footprint "eagle-import:MX-1U-LED")
      (libsource (lib "eagle-import") (part "KEYSWITCH-LED-MX-1U-LED"))
    )
    (comp (ref "K")
      (value "KEYSWITCH-LED-MX-1U-LED")
      (footprint "eagle-import:MX-1U-LED")
      (libsource (lib "eagle-import") (part "KEYSWITCH-LED-MX-1U-LED"))
    )
    (comp (ref "L")
      (value "KEYSWITCH-LED-MX-1U-LED")
      (footprint "eagle-import:MX-1U-LED")
      (libsource (lib "eagle-import") (part "KEYSWITCH-LED-MX-1U-LED"))
    )
    (comp (ref "LALT")
      (value "KEYSWITCH-LED-MX-1U-LED")
      (footprint "eagle-import:MX-1U-LED")
      (libsource (lib "eagle-import") (part "KEYSWITCH-LED-MX-1U-LED"))
    )
    (comp (ref "LARROW")
      (value "KEYSWITCH-LED-MX-1U-LED")
      (footprint "eagle-import:MX-1U-LED")
      (libsource (lib "eagle-import") (part "KEYSWITCH-LED-MX-1U-LED"))
    )
    (comp (ref "LCTRL")
      (value "KEYSWITCH-LED-MX-1U-LED")
      (footprint "eagle-import:MX-1U-LED")
      (libsource (lib "eagle-import") (part "KEYSWITCH-LED-MX-1U-LED"))
    )
    (comp (ref "LSHIFT")
      (value "KEYSWITCH-LED-MX-2U-LED")
      (footprint "eagle-import:MX-2U-LED")
      (libsource (lib "eagle-import") (part "KEYSWITCH-LED-MX-2U-LED"))
    )
    (comp (ref "M")
      (value "KEYSWITCH-LED-MX-1U-LED")
      (footprint "eagle-import:MX-1U-LED")
      (libsource (lib "eagle-import") (part "KEYSWITCH-LED-MX-1U-LED"))
    )
    (comp (ref "MENU")
      (value "KEYSWITCH-LED-MX-1U-LED")
      (footprint "eagle-import:MX-1U-LED")
      (libsource (lib "eagle-import") (part "KEYSWITCH-LED-MX-1U-LED"))
    )
    (comp (ref "N")
      (value "KEYSWITCH-LED-MX-1U-LED")
      (footprint "eagle-import:MX-1U-LED")
      (libsource (lib "eagle-import") (part "KEYSWITCH-LED-MX-1U-LED"))
    )
    (comp (ref "NUM*")
      (value "KEYSWITCH-LED-MX-1U-LED")
      (footprint "eagle-import:MX-1U-LED")
      (libsource (lib "eagle-import") (part "KEYSWITCH-LED-MX-1U-LED"))
    )
    (comp (ref "NUM+")
      (value "KEYSWITCH-LED-MX-2U-LED")
      (footprint "eagle-import:MX-2U-LED")
      (libsource (lib "eagle-import") (part "KEYSWITCH-LED-MX-2U-LED"))
    )
    (comp (ref "NUM-")
      (value "KEYSWITCH-LED-MX-1U-LED")
      (footprint "eagle-import:MX-1U-LED")
      (libsource (lib "eagle-import") (part "KEYSWITCH-LED-MX-1U-LED"))
    )
    (comp (ref "NUM-LED")
      (value "Num Lock")
      (footprint "eagle-import:LED3MM")
      (libsource (lib "eagle-import") (part "LED3MM"))
    )
    (comp (ref "NUM.")
      (value "KEYSWITCH-LED-MX-1U-LED")
      (footprint "eagle-import:MX-1U-LED")
      (libsource (lib "eagle-import") (part "KEYSWITCH-LED-MX-1U-LED"))
    )
    (comp (ref "NUM/")
      (value "KEYSWITCH-LED-MX-1U-LED")
      (footprint "eagle-import:MX-1U-LED")
      (libsource (lib "eagle-import") (part "KEYSWITCH-LED-MX-1U-LED"))
    )
    (comp (ref "NUM0")
      (value "KEYSWITCH-LED-MX-2U-LED")
      (footprint "eagle-import:MX-2U-LED")
      (libsource (lib "eagle-import") (part "KEYSWITCH-LED-MX-2U-LED"))
    )
    (comp (ref "NUM1")
      (value "KEYSWITCH-LED-MX-1U-LED")
      (footprint "eagle-import:MX-1U-LED")
      (libsource (lib "eagle-import") (part "KEYSWITCH-LED-MX-1U-LED"))
    )
    (comp (ref "NUM2")
      (value "KEYSWITCH-LED-MX-1U-LED")
      (footprint "eagle-import:MX-1U-LED")
      (libsource (lib "eagle-import") (part "KEYSWITCH-LED-MX-1U-LED"))
    )
    (comp (ref "NUM3")
      (value "KEYSWITCH-LED-MX-1U-LED")
      (footprint "eagle-import:MX-1U-LED")
      (libsource (lib "eagle-import") (part "KEYSWITCH-LED-MX-1U-LED"))
    )
    (comp (ref "NUM4")
      (value "KEYSWITCH-LED-MX-1U-LED")
      (footprint "eagle-import:MX-1U-LED")
      (libsource (lib "eagle-import") (part "KEYSWITCH-LED-MX-1U-LED"))
    )
    (comp (ref "NUM5")
      (value "KEYSWITCH-LED-MX-1U-LED")
      (footprint "eagle-import:MX-1U-LED")
      (libsource (lib "eagle-import") (part "KEYSWITCH-LED-MX-1U-LED"))
    )
    (comp (ref "NUM6")
      (value "KEYSWITCH-LED-MX-1U-LED")
      (footprint "eagle-import:MX-1U-LED")
      (libsource (lib "eagle-import") (part "KEYSWITCH-LED-MX-1U-LED"))
    )
    (comp (ref "NUM7")
      (value "KEYSWITCH-LED-MX-1U-LED")
      (footprint "eagle-import:MX-1U-LED")
      (libsource (lib "eagle-import") (part "KEYSWITCH-LED-MX-1U-LED"))
    )
    (comp (ref "NUM8")
      (value "KEYSWITCH-LED-MX-1U-LED")
      (footprint "eagle-import:MX-1U-LED")
      (libsource (lib "eagle-import") (part "KEYSWITCH-LED-MX-1U-LED"))
    )
    (comp (ref "NUM9")
      (value "KEYSWITCH-LED-MX-1U-LED")
      (footprint "eagle-import:MX-1U-LED")
      (libsource (lib "eagle-import") (part "KEYSWITCH-LED-MX-1U-LED"))
    )
    (comp (ref "NUMENTER")
      (value "KEYSWITCH-LED-MX-2U-LED")
      (footprint "eagle-import:MX-2U-LED")
      (libsource (lib "eagle-import") (part "KEYSWITCH-LED-MX-2U-LED"))
    )
    (comp (ref "NUMLK")
      (value "KEYSWITCH-LED-MX-1U-LED")
      (footprint "eagle-import:MX-1U-LED")
      (libsource (lib "eagle-import") (part "KEYSWITCH-LED-MX-1U-LED"))
    )
    (comp (ref "O")
      (value "KEYSWITCH-LED-MX-1U-LED")
      (footprint "eagle-import:MX-1U-LED")
      (libsource (lib "eagle-import") (part "KEYSWITCH-LED-MX-1U-LED"))
    )
    (comp (ref "P")
      (value "KEYSWITCH-LED-MX-1U-LED")
      (footprint "eagle-import:MX-1U-LED")
      (libsource (lib "eagle-import") (part "KEYSWITCH-LED-MX-1U-LED"))
    )
    (comp (ref "PAUSE")
      (value "KEYSWITCH-LED-MX-1U-LED")
      (footprint "eagle-import:MX-1U-LED")
      (libsource (lib "eagle-import") (part "KEYSWITCH-LED-MX-1U-LED"))
    )
    (comp (ref "PGDN")
      (value "KEYSWITCH-LED-MX-1U-LED")
      (footprint "eagle-import:MX-1U-LED")
      (libsource (lib "eagle-import") (part "KEYSWITCH-LED-MX-1U-LED"))
    )
    (comp (ref "PGUP\\")
      (value "KEYSWITCH-LED-MX-1U-LED")
      (footprint "eagle-import:MX-1U-LED")
      (libsource (lib "eagle-import") (part "KEYSWITCH-LED-MX-1U-LED"))
    )
    (comp (ref "PRTSC")
      (value "KEYSWITCH-LED-MX-1U-LED")
      (footprint "eagle-import:MX-1U-LED")
      (libsource (lib "eagle-import") (part "KEYSWITCH-LED-MX-1U-LED"))
    )
    (comp (ref "PWR")
      (value "JP1E")
      (footprint "eagle-import:JP1")
      (libsource (lib "eagle-import") (part "JP1E"))
    )
    (comp (ref "Q")
      (value "KEYSWITCH-LED-MX-1U-LED")
      (footprint "eagle-import:MX-1U-LED")
      (libsource (lib "eagle-import") (part "KEYSWITCH-LED-MX-1U-LED"))
    )
    (comp (ref "R")
      (value "KEYSWITCH-LED-MX-1U-LED")
      (footprint "eagle-import:MX-1U-LED")
      (libsource (lib "eagle-import") (part "KEYSWITCH-LED-MX-1U-LED"))
    )
    (comp (ref "R1")
      (value "100~Ω")
      (footprint "eagle-import:0204_7")
      (libsource (lib "eagle-import") (part "resistor_348_R-US_0204/7"))
    )
    (comp (ref "R2")
      (value "100~Ω")
      (footprint "eagle-import:0204_7")
      (libsource (lib "eagle-import") (part "resistor_348_R-US_0204/7"))
    )
    (comp (ref "R3")
      (value "100~Ω")
      (footprint "eagle-import:0204_7")
      (libsource (lib "eagle-import") (part "resistor_348_R-US_0204/7"))
    )
    (comp (ref "R4")
      (value "9KΩ")
      (footprint "eagle-import:0204_7")
      (libsource (lib "eagle-import") (part "R-US_0204/7"))
    )
    (comp (ref "R5")
      (value "9KΩ")
      (footprint "eagle-import:0204_7")
      (libsource (lib "eagle-import") (part "R-US_0204/7"))
    )
    (comp (ref "RALT")
      (value "KEYSWITCH-LED-MX-1U-LED")
      (footprint "eagle-import:MX-1U-LED")
      (libsource (lib "eagle-import") (part "KEYSWITCH-LED-MX-1U-LED"))
    )
    (comp (ref "RARROW")
      (value "KEYSWITCH-LED-MX-1U-LED")
      (footprint "eagle-import:MX-1U-LED")
      (libsource (lib "eagle-import") (part "KEYSWITCH-LED-MX-1U-LED"))
    )
    (comp (ref "RCTRL")
      (value "KEYSWITCH-LED-MX-1U-LED")
      (footprint "eagle-import:MX-1U-LED")
      (libsource (lib "eagle-import") (part "KEYSWITCH-LED-MX-1U-LED"))
    )
    (comp (ref "RSHIFT")
      (value "KEYSWITCH-LED-MX-2U-LED")
      (footprint "eagle-import:MX-2U-LED")
      (libsource (lib "eagle-import") (part "KEYSWITCH-LED-MX-2U-LED"))
    )
    (comp (ref "RWIN")
      (value "KEYSWITCH-LED-MX-1U-LED")
      (footprint "eagle-import:MX-1U-LED")
      (libsource (lib "eagle-import") (part "KEYSWITCH-LED-MX-1U-LED"))
    )
    (comp (ref "S")
      (value "KEYSWITCH-LED-MX-1U-LED")
      (footprint "eagle-import:MX-1U-LED")
      (libsource (lib "eagle-import") (part "KEYSWITCH-LED-MX-1U-LED"))
    )
    (comp (ref "SBAR")
      (value "KEYSWITCH-LED-MX-6.25U-LED")
      (footprint "eagle-import:MX-6.25U-LED")
      (libsource (lib "eagle-import") (part "KEYSWITCH-LED-MX-6.25U-LED"))
    )
    (comp (ref "SCOLON")
      (value "KEYSWITCH-LED-MX-1U-LED")
      (footprint "eagle-import:MX-1U-LED")
      (libsource (lib "eagle-import") (part "KEYSWITCH-LED-MX-1U-LED"))
    )
    (comp (ref "SCRLOCK")
      (value "KEYSWITCH-LED-MX-1U-LED")
      (footprint "eagle-import:MX-1U-LED")
      (libsource (lib "eagle-import") (part "KEYSWITCH-LED-MX-1U-LED"))
    )
    (comp (ref "SCROLL-LED")
      (value "Scroll Lock")
      (footprint "eagle-import:LED3MM")
      (libsource (lib "eagle-import") (part "LED3MM"))
    )
    (comp (ref "SV1")
      (value "MA04-2")
      (footprint "eagle-import:MA04-2")
      (libsource (lib "eagle-import") (part "MA04-2"))
    )
    (comp (ref "T")
      (value "KEYSWITCH-LED-MX-1U-LED")
      (footprint "eagle-import:MX-1U-LED")
      (libsource (lib "eagle-import") (part "KEYSWITCH-LED-MX-1U-LED"))
    )
    (comp (ref "TAB")
      (value "KEYSWITCH-LED-MX-1U-LED")
      (footprint "eagle-import:MX-1U-LED")
      (libsource (lib "eagle-import") (part "KEYSWITCH-LED-MX-1U-LED"))
    )
    (comp (ref "U")
      (value "KEYSWITCH-LED-MX-1U-LED")
      (footprint "eagle-import:MX-1U-LED")
      (libsource (lib "eagle-import") (part "KEYSWITCH-LED-MX-1U-LED"))
    )
    (comp (ref "U$1")
      (value "TEENSY2.0++")
      (footprint "eagle-import:TEENSY2.0++")
      (libsource (lib "eagle-import") (part "TEENSY2.0++"))
    )
    (comp (ref "UARROW")
      (value "KEYSWITCH-LED-MX-1U-LED")
      (footprint "eagle-import:MX-1U-LED")
      (libsource (lib "eagle-import") (part "KEYSWITCH-LED-MX-1U-LED"))
    )
    (comp (ref "V")
      (value "KEYSWITCH-LED-MX-1U-LED")
      (footprint "eagle-import:MX-1U-LED")
      (libsource (lib "eagle-import") (part "KEYSWITCH-LED-MX-1U-LED"))
    )
    (comp (ref "W")
      (value "KEYSWITCH-LED-MX-1U-LED")
      (footprint "eagle-import:MX-1U-LED")
      (libsource (lib "eagle-import") (part "KEYSWITCH-LED-MX-1U-LED"))
    )
    (comp (ref "WIN")
      (value "KEYSWITCH-LED-MX-1U-LED")
      (footprint "eagle-import:MX-1U-LED")
      (libsource (lib "eagle-import") (part "KEYSWITCH-LED-MX-1U-LED"))
    )
    (comp (ref "X")
      (value "KEYSWITCH-LED-MX-1U-LED")
      (footprint "eagle-import:MX-1U-LED")
      (libsource (lib "eagle-import") (part "KEYSWITCH-LED-MX-1U-LED"))
    )
    (comp (ref "Y")
      (value "KEYSWITCH-LED-MX-1U-LED")
      (footprint "eagle-import:MX-1U-LED")
      (libsource (lib "eagle-import") (part "KEYSWITCH-LED-MX-1U-LED"))
    )
    (comp (ref "Z")
      (value "KEYSWITCH-LED-MX-1U-LED")
      (footprint "eagle-import:MX-1U-LED")
      (libsource (lib "eagle-import") (part "KEYSWITCH-LED-MX-1U-LED"))
    )
    (comp (ref "[")
      (value "KEYSWITCH-LED-MX-1U-LED")
      (footprint "eagle-import:MX-1U-LED")
      (libsource (lib "eagle-import") (part "KEYSWITCH-LED-MX-1U-LED"))
    )
    (comp (ref "\\\\")
      (value "KEYSWITCH-LED-MX-1U-LED")
      (footprint "eagle-import:MX-1U-LED")
      (libsource (lib "eagle-import") (part "KEYSWITCH-LED-MX-1U-LED"))
    )
    (comp (ref "]")
      (value "KEYSWITCH-LED-MX-1U-LED")
      (footprint "eagle-import:MX-1U-LED")
      (libsource (lib "eagle-import") (part "KEYSWITCH-LED-MX-1U-LED"))
    )
    (comp (ref "`")
      (value "KEYSWITCH-LED-MX-1U-LED")
      (footprint "eagle-import:MX-1U-LED")
      (libsource (lib "eagle-import") (part "KEYSWITCH-LED-MX-1U-LED"))
    )
  )
  (nets
    (net (code "1") (name "GND") (class "Default")
      (node (ref "C1") (pin "2") (pinfunction "2_2") (pintype "passive"))
      (node (ref "C2") (pin "2") (pinfunction "2_2") (pintype "passive"))
      (node (ref "H1") (pin "B2,8") (pinfunction "MOUNT_B2,8") (pintype "passive"))
      (node (ref "H2") (pin "B2,8") (pinfunction "MOUNT_B2,8") (pintype "passive"))
      (node (ref "H3") (pin "B2,8") (pinfunction "MOUNT_B2,8") (pintype "passive"))
      (node (ref "H4") (pin "B2,8") (pinfunction "MOUNT_B2,8") (pintype "passive"))
      (node (ref "H5") (pin "B2,8") (pinfunction "MOUNT_B2,8") (pintype "passive"))
      (node (ref "H6") (pin "B2,8") (pinfunction "MOUNT_B2,8") (pintype "passive"))
      (node (ref "IC1") (pin "4") (pinfunction "GND_4") (pintype "power_in"))
      (node (ref "IC1") (pin "9") (pinfunction "GND_9") (pintype "power_in"))
      (node (ref "IC2") (pin "4") (pinfunction "GND_4") (pintype "power_in"))
      (node (ref "IC2") (pin "9") (pinfunction "GND_9") (pintype "power_in"))
      (node (ref "PWR") (pin "1") (pinfunction "1_1") (pintype "passive"))
      (node (ref "R1") (pin "1") (pinfunction "1_1") (pintype "passive"))
      (node (ref "R2") (pin "1") (pinfunction "1_1") (pintype "passive"))
      (node (ref "R3") (pin "1") (pinfunction "1_1") (pintype "passive"))
      (node (ref "U$1") (pin "GND") (pinfunction "_GND_GND") (pintype "power_in"))
      (node (ref "U$1") (pin "GND2") (pinfunction "_GND2_GND2") (pintype "power_in"))
      (node (ref "U$1") (pin "GRND1") (pinfunction "_GND1_GRND1") (pintype "power_in"))
    )
    (net (code "2") (name "Net-('-P0)") (class "Default")
      (node (ref "'") (pin "MX1") (pinfunction "P0_MX1") (pintype "bidirectional"))
      (node (ref "D311") (pin "A") (pinfunction "A_A") (pintype "passive"))
    )
    (net (code "3") (name "Net-('-P1)") (class "Default")
      (node (ref "'") (pin "MX2") (pinfunction "P1_MX2") (pintype "bidirectional"))
      (node (ref "-") (pin "MX2") (pinfunction "P1_MX2") (pintype "bidirectional"))
      (node (ref "F11") (pin "MX2") (pinfunction "P1_MX2") (pintype "bidirectional"))
      (node (ref "RWIN") (pin "MX2") (pinfunction "P1_MX2") (pintype "bidirectional"))
      (node (ref "U$1") (pin "E0") (pinfunction "_E0_E0") (pintype "bidirectional"))
      (node (ref "[") (pin "MX2") (pinfunction "P1_MX2") (pintype "bidirectional"))
    )
    (net (code "4") (name "Net-(,-P0)") (class "Default")
      (node (ref ",") (pin "MX1") (pinfunction "P0_MX1") (pintype "bidirectional"))
      (node (ref "D408") (pin "A") (pinfunction "A_A") (pintype "passive"))
    )
    (net (code "5") (name "Net-(,-P1)") (class "Default")
      (node (ref ",") (pin "MX2") (pinfunction "P1_MX2") (pintype "bidirectional"))
      (node (ref "8") (pin "MX2") (pinfunction "P1_MX2") (pintype "bidirectional"))
      (node (ref "F8") (pin "MX2") (pinfunction "P1_MX2") (pintype "bidirectional"))
      (node (ref "I") (pin "MX2") (pinfunction "P1_MX2") (pintype "bidirectional"))
      (node (ref "K") (pin "MX2") (pinfunction "P1_MX2") (pintype "bidirectional"))
      (node (ref "U$1") (pin "D5") (pinfunction "_D5_D5") (pintype "bidirectional"))
    )
    (net (code "6") (name "Net-(--P0)") (class "Default")
      (node (ref "-") (pin "MX1") (pinfunction "P0_MX1") (pintype "bidirectional"))
      (node (ref "D111") (pin "A") (pinfunction "A_A") (pintype "passive"))
    )
    (net (code "7") (name "Net-(.-P0)") (class "Default")
      (node (ref ".") (pin "MX1") (pinfunction "P0_MX1") (pintype "bidirectional"))
      (node (ref "D409") (pin "A") (pinfunction "A_A") (pintype "passive"))
    )
    (net (code "8") (name "Net-(.-P1)") (class "Default")
      (node (ref ".") (pin "MX2") (pinfunction "P1_MX2") (pintype "bidirectional"))
      (node (ref "9") (pin "MX2") (pinfunction "P1_MX2") (pintype "bidirectional"))
      (node (ref "F9") (pin "MX2") (pinfunction "P1_MX2") (pintype "bidirectional"))
      (node (ref "L") (pin "MX2") (pinfunction "P1_MX2") (pintype "bidirectional"))
      (node (ref "O") (pin "MX2") (pinfunction "P1_MX2") (pintype "bidirectional"))
      (node (ref "U$1") (pin "B4") (pinfunction "_B4_B4") (pintype "bidirectional"))
    )
    (net (code "9") (name "Net-(/-P0)") (class "Default")
      (node (ref "/") (pin "MX1") (pinfunction "P0_MX1") (pintype "bidirectional"))
      (node (ref "D410") (pin "A") (pinfunction "A_A") (pintype "passive"))
    )
    (net (code "10") (name "Net-(/-P1)") (class "Default")
      (node (ref "/") (pin "MX2") (pinfunction "P1_MX2") (pintype "bidirectional"))
      (node (ref "0") (pin "MX2") (pinfunction "P1_MX2") (pintype "bidirectional"))
      (node (ref "F10") (pin "MX2") (pinfunction "P1_MX2") (pintype "bidirectional"))
      (node (ref "P") (pin "MX2") (pinfunction "P1_MX2") (pintype "bidirectional"))
      (node (ref "RALT") (pin "MX2") (pinfunction "P1_MX2") (pintype "bidirectional"))
      (node (ref "SCOLON") (pin "MX2") (pinfunction "P1_MX2") (pintype "bidirectional"))
      (node (ref "U$1") (pin "D7") (pinfunction "_D7_D7") (pintype "bidirectional"))
    )
    (net (code "11") (name "Net-(0-P0)") (class "Default")
      (node (ref "0") (pin "MX1") (pinfunction "P0_MX1") (pintype "bidirectional"))
      (node (ref "D110") (pin "A") (pinfunction "A_A") (pintype "passive"))
    )
    (net (code "12") (name "Net-(1-P0)") (class "Default")
      (node (ref "1") (pin "MX1") (pinfunction "P0_MX1") (pintype "bidirectional"))
      (node (ref "D101") (pin "A") (pinfunction "A_A") (pintype "passive"))
    )
    (net (code "13") (name "Net-(1-P1)") (class "Default")
      (node (ref "1") (pin "MX2") (pinfunction "P1_MX2") (pintype "bidirectional"))
      (node (ref "A") (pin "MX2") (pinfunction "P1_MX2") (pintype "bidirectional"))
      (node (ref "F1") (pin "MX2") (pinfunction "P1_MX2") (pintype "bidirectional"))
      (node (ref "Q") (pin "MX2") (pinfunction "P1_MX2") (pintype "bidirectional"))
      (node (ref "U$1") (pin "B5") (pinfunction "_B5_B5") (pintype "bidirectional"))
      (node (ref "WIN") (pin "MX2") (pinfunction "P1_MX2") (pintype "bidirectional"))
      (node (ref "Z") (pin "MX2") (pinfunction "P1_MX2") (pintype "bidirectional"))
    )
    (net (code "14") (name "Net-(2-P0)") (class "Default")
      (node (ref "2") (pin "MX1") (pinfunction "P0_MX1") (pintype "bidirectional"))
      (node (ref "D102") (pin "A") (pinfunction "A_A") (pintype "passive"))
    )
    (net (code "15") (name "Net-(2-P1)") (class "Default")
      (node (ref "2") (pin "MX2") (pinfunction "P1_MX2") (pintype "bidirectional"))
      (node (ref "F2") (pin "MX2") (pinfunction "P1_MX2") (pintype "bidirectional"))
      (node (ref "LALT") (pin "MX2") (pinfunction "P1_MX2") (pintype "bidirectional"))
      (node (ref "S") (pin "MX2") (pinfunction "P1_MX2") (pintype "bidirectional"))
      (node (ref "U$1") (pin "B7") (pinfunction "_B7_B7") (pintype "bidirectional"))
      (node (ref "W") (pin "MX2") (pinfunction "P1_MX2") (pintype "bidirectional"))
      (node (ref "X") (pin "MX2") (pinfunction "P1_MX2") (pintype "bidirectional"))
    )
    (net (code "16") (name "Net-(3-P0)") (class "Default")
      (node (ref "3") (pin "MX1") (pinfunction "P0_MX1") (pintype "bidirectional"))
      (node (ref "D103") (pin "A") (pinfunction "A_A") (pintype "passive"))
    )
    (net (code "17") (name "Net-(3-P1)") (class "Default")
      (node (ref "3") (pin "MX2") (pinfunction "P1_MX2") (pintype "bidirectional"))
      (node (ref "C") (pin "MX2") (pinfunction "P1_MX2") (pintype "bidirectional"))
      (node (ref "D") (pin "MX2") (pinfunction "P1_MX2") (pintype "bidirectional"))
      (node (ref "E") (pin "MX2") (pinfunction "P1_MX2") (pintype "bidirectional"))
      (node (ref "F3") (pin "MX2") (pinfunction "P1_MX2") (pintype "bidirectional"))
      (node (ref "U$1") (pin "D0") (pinfunction "_D0_D0") (pintype "bidirectional"))
    )
    (net (code "18") (name "Net-(4-P0)") (class "Default")
      (node (ref "4") (pin "MX1") (pinfunction "P0_MX1") (pintype "bidirectional"))
      (node (ref "D104") (pin "A") (pinfunction "A_A") (pintype "passive"))
    )
    (net (code "19") (name "Net-(4-P1)") (class "Default")
      (node (ref "4") (pin "MX2") (pinfunction "P1_MX2") (pintype "bidirectional"))
      (node (ref "F") (pin "MX2") (pinfunction "P1_MX2") (pintype "bidirectional"))
      (node (ref "F4") (pin "MX2") (pinfunction "P1_MX2") (pintype "bidirectional"))
      (node (ref "R") (pin "MX2") (pinfunction "P1_MX2") (pintype "bidirectional"))
      (node (ref "U$1") (pin "D1") (pinfunction "_D1_D1") (pintype "bidirectional"))
      (node (ref "V") (pin "MX2") (pinfunction "P1_MX2") (pintype "bidirectional"))
    )
    (net (code "20") (name "Net-(5-P0)") (class "Default")
      (node (ref "5") (pin "MX1") (pinfunction "P0_MX1") (pintype "bidirectional"))
      (node (ref "D105") (pin "A") (pinfunction "A_A") (pintype "passive"))
    )
    (net (code "21") (name "Net-(5-P1)") (class "Default")
      (node (ref "5") (pin "MX2") (pinfunction "P1_MX2") (pintype "bidirectional"))
      (node (ref "B") (pin "MX2") (pinfunction "P1_MX2") (pintype "bidirectional"))
      (node (ref "F5") (pin "MX2") (pinfunction "P1_MX2") (pintype "bidirectional"))
      (node (ref "G") (pin "MX2") (pinfunction "P1_MX2") (pintype "bidirectional"))
      (node (ref "T") (pin "MX2") (pinfunction "P1_MX2") (pintype "bidirectional"))
      (node (ref "U$1") (pin "D2") (pinfunction "_D2_D2") (pintype "bidirectional"))
    )
    (net (code "22") (name "Net-(6-P0)") (class "Default")
      (node (ref "6") (pin "MX1") (pinfunction "P0_MX1") (pintype "bidirectional"))
      (node (ref "D106") (pin "A") (pinfunction "A_A") (pintype "passive"))
    )
    (net (code "23") (name "Net-(6-P1)") (class "Default")
      (node (ref "6") (pin "MX2") (pinfunction "P1_MX2") (pintype "bidirectional"))
      (node (ref "F6") (pin "MX2") (pinfunction "P1_MX2") (pintype "bidirectional"))
      (node (ref "H") (pin "MX2") (pinfunction "P1_MX2") (pintype "bidirectional"))
      (node (ref "N") (pin "MX2") (pinfunction "P1_MX2") (pintype "bidirectional"))
      (node (ref "SBAR") (pin "MX2") (pinfunction "P1_MX2") (pintype "bidirectional"))
      (node (ref "U$1") (pin "D3") (pinfunction "_D3_D3") (pintype "bidirectional"))
      (node (ref "Y") (pin "MX2") (pinfunction "P1_MX2") (pintype "bidirectional"))
    )
    (net (code "24") (name "Net-(7-P0)") (class "Default")
      (node (ref "7") (pin "MX1") (pinfunction "P0_MX1") (pintype "bidirectional"))
      (node (ref "D107") (pin "A") (pinfunction "A_A") (pintype "passive"))
    )
    (net (code "25") (name "Net-(7-P1)") (class "Default")
      (node (ref "7") (pin "MX2") (pinfunction "P1_MX2") (pintype "bidirectional"))
      (node (ref "F7") (pin "MX2") (pinfunction "P1_MX2") (pintype "bidirectional"))
      (node (ref "J") (pin "MX2") (pinfunction "P1_MX2") (pintype "bidirectional"))
      (node (ref "M") (pin "MX2") (pinfunction "P1_MX2") (pintype "bidirectional"))
      (node (ref "U") (pin "MX2") (pinfunction "P1_MX2") (pintype "bidirectional"))
      (node (ref "U$1") (pin "D4") (pinfunction "_D4_D4") (pintype "bidirectional"))
    )
    (net (code "26") (name "Net-(8-P0)") (class "Default")
      (node (ref "8") (pin "MX1") (pinfunction "P0_MX1") (pintype "bidirectional"))
      (node (ref "D108") (pin "A") (pinfunction "A_A") (pintype "passive"))
    )
    (net (code "27") (name "Net-(9-P0)") (class "Default")
      (node (ref "9") (pin "MX1") (pinfunction "P0_MX1") (pintype "bidirectional"))
      (node (ref "D109") (pin "A") (pinfunction "A_A") (pintype "passive"))
    )
    (net (code "28") (name "Net-(=-P0)") (class "Default")
      (node (ref "=") (pin "MX1") (pinfunction "P0_MX1") (pintype "bidirectional"))
      (node (ref "D112") (pin "A") (pinfunction "A_A") (pintype "passive"))
    )
    (net (code "29") (name "Net-(=-P1)") (class "Default")
      (node (ref "=") (pin "MX2") (pinfunction "P1_MX2") (pintype "bidirectional"))
      (node (ref "F12") (pin "MX2") (pinfunction "P1_MX2") (pintype "bidirectional"))
      (node (ref "MENU") (pin "MX2") (pinfunction "P1_MX2") (pintype "bidirectional"))
      (node (ref "U$1") (pin "E1") (pinfunction "_E1_E1") (pintype "bidirectional"))
      (node (ref "]") (pin "MX2") (pinfunction "P1_MX2") (pintype "bidirectional"))
    )
    (net (code "30") (name "Net-(A-P0)") (class "Default")
      (node (ref "A") (pin "MX1") (pinfunction "P0_MX1") (pintype "bidirectional"))
      (node (ref "D301") (pin "A") (pinfunction "A_A") (pintype "passive"))
    )
    (net (code "31") (name "Net-(B-P0)") (class "Default")
      (node (ref "B") (pin "MX1") (pinfunction "P0_MX1") (pintype "bidirectional"))
      (node (ref "D405") (pin "A") (pinfunction "A_A") (pintype "passive"))
    )
    (net (code "32") (name "Net-(BKSPACE-P0)") (class "Default")
      (node (ref "BKSPACE") (pin "MX1") (pinfunction "P0_MX1") (pintype "bidirectional"))
      (node (ref "D113") (pin "A") (pinfunction "A_A") (pintype "passive"))
    )
    (net (code "33") (name "Net-(BKSPACE-P1)") (class "Default")
      (node (ref "BKSPACE") (pin "MX2") (pinfunction "P1_MX2") (pintype "bidirectional"))
      (node (ref "ENTER") (pin "MX2") (pinfunction "P1_MX2") (pintype "bidirectional"))
      (node (ref "RCTRL") (pin "MX2") (pinfunction "P1_MX2") (pintype "bidirectional"))
      (node (ref "RSHIFT") (pin "MX2") (pinfunction "P1_MX2") (pintype "bidirectional"))
      (node (ref "U$1") (pin "C0") (pinfunction "_C0_C0") (pintype "bidirectional"))
      (node (ref "\\\\") (pin "MX2") (pinfunction "P1_MX2") (pintype "bidirectional"))
    )
    (net (code "34") (name "Net-(C-P0)") (class "Default")
      (node (ref "C") (pin "MX1") (pinfunction "P0_MX1") (pintype "bidirectional"))
      (node (ref "D403") (pin "A") (pinfunction "A_A") (pintype "passive"))
    )
    (net (code "35") (name "Net-(CAPS-LED-C)") (class "Default")
      (node (ref "CAPS-LED") (pin "K") (pinfunction "C_K") (pintype "passive"))
      (node (ref "R2") (pin "2") (pinfunction "2_2") (pintype "passive"))
    )
    (net (code "36") (name "Net-(CAPSLK-P0)") (class "Default")
      (node (ref "CAPSLK") (pin "MX1") (pinfunction "P0_MX1") (pintype "bidirectional"))
      (node (ref "D300") (pin "A") (pinfunction "A_A") (pintype "passive"))
    )
    (net (code "37") (name "Net-(CAPSLK-P1)") (class "Default")
      (node (ref "CAPSLK") (pin "MX2") (pinfunction "P1_MX2") (pintype "bidirectional"))
      (node (ref "ESC") (pin "MX2") (pinfunction "P1_MX2") (pintype "bidirectional"))
      (node (ref "LCTRL") (pin "MX2") (pinfunction "P1_MX2") (pintype "bidirectional"))
      (node (ref "LSHIFT") (pin "MX2") (pinfunction "P1_MX2") (pintype "bidirectional"))
      (node (ref "TAB") (pin "MX2") (pinfunction "P1_MX2") (pintype "bidirectional"))
      (node (ref "U$1") (pin "B6") (pinfunction "_B6_B6") (pintype "bidirectional"))
      (node (ref "`") (pin "MX2") (pinfunction "P1_MX2") (pintype "bidirectional"))
    )
    (net (code "38") (name "Net-(D-P0)") (class "Default")
      (node (ref "D") (pin "MX1") (pinfunction "P0_MX1") (pintype "bidirectional"))
      (node (ref "D303") (pin "A") (pinfunction "A_A") (pintype "passive"))
    )
    (net (code "39") (name "Net-(DARROW-P0)") (class "Default")
      (node (ref "D515") (pin "A") (pinfunction "A_A") (pintype "passive"))
      (node (ref "DARROW") (pin "MX1") (pinfunction "P0_MX1") (pintype "bidirectional"))
    )
    (net (code "40") (name "Net-(DARROW-P1)") (class "Default")
      (node (ref "DARROW") (pin "MX2") (pinfunction "P1_MX2") (pintype "bidirectional"))
      (node (ref "END") (pin "MX2") (pinfunction "P1_MX2") (pintype "bidirectional"))
      (node (ref "HOME") (pin "MX2") (pinfunction "P1_MX2") (pintype "bidirectional"))
      (node (ref "SCRLOCK") (pin "MX2") (pinfunction "P1_MX2") (pintype "bidirectional"))
      (node (ref "U$1") (pin "C2") (pinfunction "_C2_C2") (pintype "bidirectional"))
      (node (ref "UARROW") (pin "MX2") (pinfunction "P1_MX2") (pintype "bidirectional"))
    )
    (net (code "41") (name "Net-(DELETE-P0)") (class "Default")
      (node (ref "D214") (pin "A") (pinfunction "A_A") (pintype "passive"))
      (node (ref "DELETE") (pin "MX1") (pinfunction "P0_MX1") (pintype "bidirectional"))
    )
    (net (code "42") (name "Net-(DELETE-P1)") (class "Default")
      (node (ref "DELETE") (pin "MX2") (pinfunction "P1_MX2") (pintype "bidirectional"))
      (node (ref "INS") (pin "MX2") (pinfunction "P1_MX2") (pintype "bidirectional"))
      (node (ref "LARROW") (pin "MX2") (pinfunction "P1_MX2") (pintype "bidirectional"))
      (node (ref "PRTSC") (pin "MX2") (pinfunction "P1_MX2") (pintype "bidirectional"))
      (node (ref "U$1") (pin "C1") (pinfunction "_C1_C1") (pintype "bidirectional"))
    )
    (net (code "43") (name "Net-(E-P0)") (class "Default")
      (node (ref "D203") (pin "A") (pinfunction "A_A") (pintype "passive"))
      (node (ref "E") (pin "MX1") (pinfunction "P0_MX1") (pintype "bidirectional"))
    )
    (net (code "44") (name "Net-(END-P0)") (class "Default")
      (node (ref "D215") (pin "A") (pinfunction "A_A") (pintype "passive"))
      (node (ref "END") (pin "MX1") (pinfunction "P0_MX1") (pintype "bidirectional"))
    )
    (net (code "45") (name "Net-(ENTER-P0)") (class "Default")
      (node (ref "D313") (pin "A") (pinfunction "A_A") (pintype "passive"))
      (node (ref "ENTER") (pin "MX1") (pinfunction "P0_MX1") (pintype "bidirectional"))
    )
    (net (code "46") (name "Net-(ESC-P0)") (class "Default")
      (node (ref "D000") (pin "A") (pinfunction "A_A") (pintype "passive"))
      (node (ref "ESC") (pin "MX1") (pinfunction "P0_MX1") (pintype "bidirectional"))
    )
    (net (code "47") (name "Net-(F-P0)") (class "Default")
      (node (ref "D304") (pin "A") (pinfunction "A_A") (pintype "passive"))
      (node (ref "F") (pin "MX1") (pinfunction "P0_MX1") (pintype "bidirectional"))
    )
    (net (code "48") (name "Net-(F1-P0)") (class "Default")
      (node (ref "D001") (pin "A") (pinfunction "A_A") (pintype "passive"))
      (node (ref "F1") (pin "MX1") (pinfunction "P0_MX1") (pintype "bidirectional"))
    )
    (net (code "49") (name "Net-(F2-P0)") (class "Default")
      (node (ref "D002") (pin "A") (pinfunction "A_A") (pintype "passive"))
      (node (ref "F2") (pin "MX1") (pinfunction "P0_MX1") (pintype "bidirectional"))
    )
    (net (code "50") (name "Net-(F3-P0)") (class "Default")
      (node (ref "D003") (pin "A") (pinfunction "A_A") (pintype "passive"))
      (node (ref "F3") (pin "MX1") (pinfunction "P0_MX1") (pintype "bidirectional"))
    )
    (net (code "51") (name "Net-(F4-P0)") (class "Default")
      (node (ref "D004") (pin "A") (pinfunction "A_A") (pintype "passive"))
      (node (ref "F4") (pin "MX1") (pinfunction "P0_MX1") (pintype "bidirectional"))
    )
    (net (code "52") (name "Net-(F5-P0)") (class "Default")
      (node (ref "D005") (pin "A") (pinfunction "A_A") (pintype "passive"))
      (node (ref "F5") (pin "MX1") (pinfunction "P0_MX1") (pintype "bidirectional"))
    )
    (net (code "53") (name "Net-(F6-P0)") (class "Default")
      (node (ref "D006") (pin "A") (pinfunction "A_A") (pintype "passive"))
      (node (ref "F6") (pin "MX1") (pinfunction "P0_MX1") (pintype "bidirectional"))
    )
    (net (code "54") (name "Net-(F7-P0)") (class "Default")
      (node (ref "D007") (pin "A") (pinfunction "A_A") (pintype "passive"))
      (node (ref "F7") (pin "MX1") (pinfunction "P0_MX1") (pintype "bidirectional"))
    )
    (net (code "55") (name "Net-(F8-P0)") (class "Default")
      (node (ref "D008") (pin "A") (pinfunction "A_A") (pintype "passive"))
      (node (ref "F8") (pin "MX1") (pinfunction "P0_MX1") (pintype "bidirectional"))
    )
    (net (code "56") (name "Net-(F9-P0)") (class "Default")
      (node (ref "D009") (pin "A") (pinfunction "A_A") (pintype "passive"))
      (node (ref "F9") (pin "MX1") (pinfunction "P0_MX1") (pintype "bidirectional"))
    )
    (net (code "57") (name "Net-(F10-P0)") (class "Default")
      (node (ref "D010") (pin "A") (pinfunction "A_A") (pintype "passive"))
      (node (ref "F10") (pin "MX1") (pinfunction "P0_MX1") (pintype "bidirectional"))
    )
    (net (code "58") (name "Net-(F11-P0)") (class "Default")
      (node (ref "D011") (pin "A") (pinfunction "A_A") (pintype "passive"))
      (node (ref "F11") (pin "MX1") (pinfunction "P0_MX1") (pintype "bidirectional"))
    )
    (net (code "59") (name "Net-(F12-P0)") (class "Default")
      (node (ref "D012") (pin "A") (pinfunction "A_A") (pintype "passive"))
      (node (ref "F12") (pin "MX1") (pinfunction "P0_MX1") (pintype "bidirectional"))
    )
    (net (code "60") (name "Net-(G-P0)") (class "Default")
      (node (ref "D305") (pin "A") (pinfunction "A_A") (pintype "passive"))
      (node (ref "G") (pin "MX1") (pinfunction "P0_MX1") (pintype "bidirectional"))
    )
    (net (code "61") (name "Net-(H-P0)") (class "Default")
      (node (ref "D306") (pin "A") (pinfunction "A_A") (pintype "passive"))
      (node (ref "H") (pin "MX1") (pinfunction "P0_MX1") (pintype "bidirectional"))
    )
    (net (code "62") (name "Net-(HOME-P0)") (class "Default")
      (node (ref "D115") (pin "A") (pinfunction "A_A") (pintype "passive"))
      (node (ref "HOME") (pin "MX1") (pinfunction "P0_MX1") (pintype "bidirectional"))
    )
    (net (code "63") (name "Net-(I-P0)") (class "Default")
      (node (ref "D208") (pin "A") (pinfunction "A_A") (pintype "passive"))
      (node (ref "I") (pin "MX1") (pinfunction "P0_MX1") (pintype "bidirectional"))
    )
    (net (code "64") (name "Net-(IC1-CLK)") (class "Default")
      (node (ref "IC1") (pin "13") (pinfunction "CLK_13") (pintype "input"))
      (node (ref "IC2") (pin "13") (pinfunction "CLK_13") (pintype "input"))
      (node (ref "U$1") (pin "B0") (pinfunction "_B0_B0") (pintype "bidirectional"))
    )
    (net (code "65") (name "Net-(IC1-DIG0)") (class "Default")
      (node (ref "8") (pin "LED-") (pinfunction "LED-_LED-") (pintype "bidirectional"))
      (node (ref "CAPSLK") (pin "LED-") (pinfunction "LED-_LED-") (pintype "bidirectional"))
      (node (ref "ESC") (pin "LED-") (pinfunction "LED-_LED-") (pintype "bidirectional"))
      (node (ref "F8") (pin "LED-") (pinfunction "LED-_LED-") (pintype "bidirectional"))
      (node (ref "IC1") (pin "2") (pinfunction "DIG0_2") (pintype "output"))
      (node (ref "LCTRL") (pin "LED-") (pinfunction "LED-_LED-") (pintype "bidirectional"))
      (node (ref "LSHIFT") (pin "LED-") (pinfunction "LED-_LED-") (pintype "bidirectional"))
      (node (ref "TAB") (pin "LED-") (pinfunction "LED-_LED-") (pintype "bidirectional"))
      (node (ref "`") (pin "LED-") (pinfunction "LED-_LED-") (pintype "bidirectional"))
    )
    (net (code "66") (name "Net-(IC1-DIG1)") (class "Default")
      (node (ref "1") (pin "LED-") (pinfunction "LED-_LED-") (pintype "bidirectional"))
      (node (ref "9") (pin "LED-") (pinfunction "LED-_LED-") (pintype "bidirectional"))
      (node (ref "A") (pin "LED-") (pinfunction "LED-_LED-") (pintype "bidirectional"))
      (node (ref "F1") (pin "LED-") (pinfunction "LED-_LED-") (pintype "bidirectional"))
      (node (ref "F9") (pin "LED-") (pinfunction "LED-_LED-") (pintype "bidirectional"))
      (node (ref "IC1") (pin "11") (pinfunction "DIG1_11") (pintype "output"))
      (node (ref "Q") (pin "LED-") (pinfunction "LED-_LED-") (pintype "bidirectional"))
      (node (ref "WIN") (pin "LED-") (pinfunction "LED-_LED-") (pintype "bidirectional"))
      (node (ref "Z") (pin "LED-") (pinfunction "LED-_LED-") (pintype "bidirectional"))
    )
    (net (code "67") (name "Net-(IC1-DIG2)") (class "Default")
      (node (ref "0") (pin "LED-") (pinfunction "LED-_LED-") (pintype "bidirectional"))
      (node (ref "2") (pin "LED-") (pinfunction "LED-_LED-") (pintype "bidirectional"))
      (node (ref "F10") (pin "LED-") (pinfunction "LED-_LED-") (pintype "bidirectional"))
      (node (ref "F2") (pin "LED-") (pinfunction "LED-_LED-") (pintype "bidirectional"))
      (node (ref "IC1") (pin "6") (pinfunction "DIG2_6") (pintype "output"))
      (node (ref "LALT") (pin "LED-") (pinfunction "LED-_LED-") (pintype "bidirectional"))
      (node (ref "S") (pin "LED-") (pinfunction "LED-_LED-") (pintype "bidirectional"))
      (node (ref "W") (pin "LED-") (pinfunction "LED-_LED-") (pintype "bidirectional"))
      (node (ref "X") (pin "LED-") (pinfunction "LED-_LED-") (pintype "bidirectional"))
    )
    (net (code "68") (name "Net-(IC1-DIG3)") (class "Default")
      (node (ref "-") (pin "LED-") (pinfunction "LED-_LED-") (pintype "bidirectional"))
      (node (ref "3") (pin "LED-") (pinfunction "LED-_LED-") (pintype "bidirectional"))
      (node (ref "C") (pin "LED-") (pinfunction "LED-_LED-") (pintype "bidirectional"))
      (node (ref "D") (pin "LED-") (pinfunction "LED-_LED-") (pintype "bidirectional"))
      (node (ref "E") (pin "LED-") (pinfunction "LED-_LED-") (pintype "bidirectional"))
      (node (ref "F11") (pin "LED-") (pinfunction "LED-_LED-") (pintype "bidirectional"))
      (node (ref "F3") (pin "LED-") (pinfunction "LED-_LED-") (pintype "bidirectional"))
      (node (ref "IC1") (pin "7") (pinfunction "DIG3_7") (pintype "output"))
      (node (ref "SBAR") (pin "LED-") (pinfunction "LED-_LED-") (pintype "bidirectional"))
    )
    (net (code "69") (name "Net-(IC1-DIG4)") (class "Default")
      (node (ref "4") (pin "LED-") (pinfunction "LED-_LED-") (pintype "bidirectional"))
      (node (ref "=") (pin "LED-") (pinfunction "LED-_LED-") (pintype "bidirectional"))
      (node (ref "F") (pin "LED-") (pinfunction "LED-_LED-") (pintype "bidirectional"))
      (node (ref "F12") (pin "LED-") (pinfunction "LED-_LED-") (pintype "bidirectional"))
      (node (ref "F4") (pin "LED-") (pinfunction "LED-_LED-") (pintype "bidirectional"))
      (node (ref "IC1") (pin "3") (pinfunction "DIG4_3") (pintype "output"))
      (node (ref "R") (pin "LED-") (pinfunction "LED-_LED-") (pintype "bidirectional"))
      (node (ref "RALT") (pin "LED-") (pinfunction "LED-_LED-") (pintype "bidirectional"))
      (node (ref "V") (pin "LED-") (pinfunction "LED-_LED-") (pintype "bidirectional"))
    )
    (net (code "70") (name "Net-(IC1-DIG5)") (class "Default")
      (node (ref "5") (pin "LED-") (pinfunction "LED-_LED-") (pintype "bidirectional"))
      (node (ref "B") (pin "LED-") (pinfunction "LED-_LED-") (pintype "bidirectional"))
      (node (ref "BKSPACE") (pin "LED-") (pinfunction "LED-_LED-") (pintype "bidirectional"))
      (node (ref "F5") (pin "LED-") (pinfunction "LED-_LED-") (pintype "bidirectional"))
      (node (ref "G") (pin "LED-") (pinfunction "LED-_LED-") (pintype "bidirectional"))
      (node (ref "IC1") (pin "10") (pinfunction "DIG5_10") (pintype "output"))
      (node (ref "PRTSC") (pin "LED-") (pinfunction "LED-_LED-") (pintype "bidirectional"))
      (node (ref "RWIN") (pin "LED-") (pinfunction "LED-_LED-") (pintype "bidirectional"))
      (node (ref "T") (pin "LED-") (pinfunction "LED-_LED-") (pintype "bidirectional"))
    )
    (net (code "71") (name "Net-(IC1-DIG6)") (class "Default")
      (node (ref "6") (pin "LED-") (pinfunction "LED-_LED-") (pintype "bidirectional"))
      (node (ref "F6") (pin "LED-") (pinfunction "LED-_LED-") (pintype "bidirectional"))
      (node (ref "H") (pin "LED-") (pinfunction "LED-_LED-") (pintype "bidirectional"))
      (node (ref "IC1") (pin "5") (pinfunction "DIG6_5") (pintype "output"))
      (node (ref "INS") (pin "LED-") (pinfunction "LED-_LED-") (pintype "bidirectional"))
      (node (ref "MENU") (pin "LED-") (pinfunction "LED-_LED-") (pintype "bidirectional"))
      (node (ref "N") (pin "LED-") (pinfunction "LED-_LED-") (pintype "bidirectional"))
      (node (ref "SCRLOCK") (pin "LED-") (pinfunction "LED-_LED-") (pintype "bidirectional"))
      (node (ref "Y") (pin "LED-") (pinfunction "LED-_LED-") (pintype "bidirectional"))
    )
    (net (code "72") (name "Net-(IC1-DIG7)") (class "Default")
      (node (ref "7") (pin "LED-") (pinfunction "LED-_LED-") (pintype "bidirectional"))
      (node (ref "F7") (pin "LED-") (pinfunction "LED-_LED-") (pintype "bidirectional"))
      (node (ref "HOME") (pin "LED-") (pinfunction "LED-_LED-") (pintype "bidirectional"))
      (node (ref "IC1") (pin "8") (pinfunction "DIG7_8") (pintype "output"))
      (node (ref "J") (pin "LED-") (pinfunction "LED-_LED-") (pintype "bidirectional"))
      (node (ref "M") (pin "LED-") (pinfunction "LED-_LED-") (pintype "bidirectional"))
      (node (ref "PAUSE") (pin "LED-") (pinfunction "LED-_LED-") (pintype "bidirectional"))
      (node (ref "RCTRL") (pin "LED-") (pinfunction "LED-_LED-") (pintype "bidirectional"))
      (node (ref "U") (pin "LED-") (pinfunction "LED-_LED-") (pintype "bidirectional"))
    )
    (net (code "73") (name "Net-(IC1-DIN)") (class "Default")
      (node (ref "IC1") (pin "1") (pinfunction "DIN_1") (pintype "input"))
      (node (ref "IC2") (pin "24") (pinfunction "DOUT_24") (pintype "output"))
    )
    (net (code "74") (name "Net-(IC1-ISET)") (class "Default")
      (node (ref "IC1") (pin "18") (pinfunction "ISET_18") (pintype "input"))
      (node (ref "R4") (pin "2") (pinfunction "2_2") (pintype "passive"))
    )
    (net (code "75") (name "Net-(IC1-LOAD)") (class "Default")
      (node (ref "IC1") (pin "12") (pinfunction "LOAD_12") (pintype "input"))
      (node (ref "IC2") (pin "12") (pinfunction "LOAD_12") (pintype "input"))
      (node (ref "U$1") (pin "B1") (pinfunction "_B1_B1") (pintype "bidirectional"))
    )
    (net (code "76") (name "Net-(IC1-SEGA)") (class "Default")
      (node (ref "IC1") (pin "14") (pinfunction "SEGA_14") (pintype "output"))
      (node (ref "LALT") (pin "LED+") (pinfunction "LED+_LED+") (pintype "bidirectional"))
      (node (ref "LCTRL") (pin "LED+") (pinfunction "LED+_LED+") (pintype "bidirectional"))
      (node (ref "MENU") (pin "LED+") (pinfunction "LED+_LED+") (pintype "bidirectional"))
      (node (ref "RALT") (pin "LED+") (pinfunction "LED+_LED+") (pintype "bidirectional"))
      (node (ref "RCTRL") (pin "LED+") (pinfunction "LED+_LED+") (pintype "bidirectional"))
      (node (ref "RWIN") (pin "LED+") (pinfunction "LED+_LED+") (pintype "bidirectional"))
      (node (ref "SBAR") (pin "LED+") (pinfunction "LED+_LED+") (pintype "bidirectional"))
      (node (ref "WIN") (pin "LED+") (pinfunction "LED+_LED+") (pintype "bidirectional"))
    )
    (net (code "77") (name "Net-(IC1-SEGB)") (class "Default")
      (node (ref "B") (pin "LED+") (pinfunction "LED+_LED+") (pintype "bidirectional"))
      (node (ref "C") (pin "LED+") (pinfunction "LED+_LED+") (pintype "bidirectional"))
      (node (ref "IC1") (pin "16") (pinfunction "SEGB_16") (pintype "output"))
      (node (ref "LSHIFT") (pin "LED+") (pinfunction "LED+_LED+") (pintype "bidirectional"))
      (node (ref "M") (pin "LED+") (pinfunction "LED+_LED+") (pintype "bidirectional"))
      (node (ref "N") (pin "LED+") (pinfunction "LED+_LED+") (pintype "bidirectional"))
      (node (ref "V") (pin "LED+") (pinfunction "LED+_LED+") (pintype "bidirectional"))
      (node (ref "X") (pin "LED+") (pinfunction "LED+_LED+") (pintype "bidirectional"))
      (node (ref "Z") (pin "LED+") (pinfunction "LED+_LED+") (pintype "bidirectional"))
    )
    (net (code "78") (name "Net-(IC1-SEGC)") (class "Default")
      (node (ref "A") (pin "LED+") (pinfunction "LED+_LED+") (pintype "bidirectional"))
      (node (ref "CAPSLK") (pin "LED+") (pinfunction "LED+_LED+") (pintype "bidirectional"))
      (node (ref "D") (pin "LED+") (pinfunction "LED+_LED+") (pintype "bidirectional"))
      (node (ref "F") (pin "LED+") (pinfunction "LED+_LED+") (pintype "bidirectional"))
      (node (ref "G") (pin "LED+") (pinfunction "LED+_LED+") (pintype "bidirectional"))
      (node (ref "H") (pin "LED+") (pinfunction "LED+_LED+") (pintype "bidirectional"))
      (node (ref "IC1") (pin "20") (pinfunction "SEGC_20") (pintype "output"))
      (node (ref "J") (pin "LED+") (pinfunction "LED+_LED+") (pintype "bidirectional"))
      (node (ref "S") (pin "LED+") (pinfunction "LED+_LED+") (pintype "bidirectional"))
    )
    (net (code "79") (name "Net-(IC1-SEGD)") (class "Default")
      (node (ref "E") (pin "LED+") (pinfunction "LED+_LED+") (pintype "bidirectional"))
      (node (ref "IC1") (pin "23") (pinfunction "SEGD_23") (pintype "output"))
      (node (ref "Q") (pin "LED+") (pinfunction "LED+_LED+") (pintype "bidirectional"))
      (node (ref "R") (pin "LED+") (pinfunction "LED+_LED+") (pintype "bidirectional"))
      (node (ref "T") (pin "LED+") (pinfunction "LED+_LED+") (pintype "bidirectional"))
      (node (ref "TAB") (pin "LED+") (pinfunction "LED+_LED+") (pintype "bidirectional"))
      (node (ref "U") (pin "LED+") (pinfunction "LED+_LED+") (pintype "bidirectional"))
      (node (ref "W") (pin "LED+") (pinfunction "LED+_LED+") (pintype "bidirectional"))
      (node (ref "Y") (pin "LED+") (pinfunction "LED+_LED+") (pintype "bidirectional"))
    )
    (net (code "80") (name "Net-(IC1-SEGDP)") (class "Default")
      (node (ref "-") (pin "LED+") (pinfunction "LED+_LED+") (pintype "bidirectional"))
      (node (ref "0") (pin "LED+") (pinfunction "LED+_LED+") (pintype "bidirectional"))
      (node (ref "8") (pin "LED+") (pinfunction "LED+_LED+") (pintype "bidirectional"))
      (node (ref "9") (pin "LED+") (pinfunction "LED+_LED+") (pintype "bidirectional"))
      (node (ref "=") (pin "LED+") (pinfunction "LED+_LED+") (pintype "bidirectional"))
      (node (ref "BKSPACE") (pin "LED+") (pinfunction "LED+_LED+") (pintype "bidirectional"))
      (node (ref "HOME") (pin "LED+") (pinfunction "LED+_LED+") (pintype "bidirectional"))
      (node (ref "IC1") (pin "22") (pinfunction "SEGDP_22") (pintype "output"))
      (node (ref "INS") (pin "LED+") (pinfunction "LED+_LED+") (pintype "bidirectional"))
    )
    (net (code "81") (name "Net-(IC1-SEGE)") (class "Default")
      (node (ref "1") (pin "LED+") (pinfunction "LED+_LED+") (pintype "bidirectional"))
      (node (ref "2") (pin "LED+") (pinfunction "LED+_LED+") (pintype "bidirectional"))
      (node (ref "3") (pin "LED+") (pinfunction "LED+_LED+") (pintype "bidirectional"))
      (node (ref "4") (pin "LED+") (pinfunction "LED+_LED+") (pintype "bidirectional"))
      (node (ref "5") (pin "LED+") (pinfunction "LED+_LED+") (pintype "bidirectional"))
      (node (ref "6") (pin "LED+") (pinfunction "LED+_LED+") (pintype "bidirectional"))
      (node (ref "7") (pin "LED+") (pinfunction "LED+_LED+") (pintype "bidirectional"))
      (node (ref "IC1") (pin "21") (pinfunction "SEGE_21") (pintype "output"))
      (node (ref "`") (pin "LED+") (pinfunction "LED+_LED+") (pintype "bidirectional"))
    )
    (net (code "82") (name "Net-(IC1-SEGF)") (class "Default")
      (node (ref "ESC") (pin "LED+") (pinfunction "LED+_LED+") (pintype "bidirectional"))
      (node (ref "F1") (pin "LED+") (pinfunction "LED+_LED+") (pintype "bidirectional"))
      (node (ref "F2") (pin "LED+") (pinfunction "LED+_LED+") (pintype "bidirectional"))
      (node (ref "F3") (pin "LED+") (pinfunction "LED+_LED+") (pintype "bidirectional"))
      (node (ref "F4") (pin "LED+") (pinfunction "LED+_LED+") (pintype "bidirectional"))
      (node (ref "F5") (pin "LED+") (pinfunction "LED+_LED+") (pintype "bidirectional"))
      (node (ref "F6") (pin "LED+") (pinfunction "LED+_LED+") (pintype "bidirectional"))
      (node (ref "F7") (pin "LED+") (pinfunction "LED+_LED+") (pintype "bidirectional"))
      (node (ref "IC1") (pin "15") (pinfunction "SEGF_15") (pintype "output"))
    )
    (net (code "83") (name "Net-(IC1-SEGG)") (class "Default")
      (node (ref "F10") (pin "LED+") (pinfunction "LED+_LED+") (pintype "bidirectional"))
      (node (ref "F11") (pin "LED+") (pinfunction "LED+_LED+") (pintype "bidirectional"))
      (node (ref "F12") (pin "LED+") (pinfunction "LED+_LED+") (pintype "bidirectional"))
      (node (ref "F8") (pin "LED+") (pinfunction "LED+_LED+") (pintype "bidirectional"))
      (node (ref "F9") (pin "LED+") (pinfunction "LED+_LED+") (pintype "bidirectional"))
      (node (ref "IC1") (pin "17") (pinfunction "SEGG_17") (pintype "output"))
      (node (ref "PAUSE") (pin "LED+") (pinfunction "LED+_LED+") (pintype "bidirectional"))
      (node (ref "PRTSC") (pin "LED+") (pinfunction "LED+_LED+") (pintype "bidirectional"))
      (node (ref "SCRLOCK") (pin "LED+") (pinfunction "LED+_LED+") (pintype "bidirectional"))
    )
    (net (code "84") (name "Net-(IC2-DIG0)") (class "Default")
      (node (ref ",") (pin "LED-") (pinfunction "LED-_LED-") (pintype "bidirectional"))
      (node (ref "I") (pin "LED-") (pinfunction "LED-_LED-") (pintype "bidirectional"))
      (node (ref "IC2") (pin "2") (pinfunction "DIG0_2") (pintype "output"))
      (node (ref "K") (pin "LED-") (pinfunction "LED-_LED-") (pintype "bidirectional"))
      (node (ref "LARROW") (pin "LED-") (pinfunction "LED-_LED-") (pintype "bidirectional"))
      (node (ref "PGDN") (pin "LED-") (pinfunction "LED-_LED-") (pintype "bidirectional"))
      (node (ref "PGUP\\") (pin "LED-") (pinfunction "LED-_LED-") (pintype "bidirectional"))
    )
    (net (code "85") (name "Net-(IC2-DIG1)") (class "Default")
      (node (ref ".") (pin "LED-") (pinfunction "LED-_LED-") (pintype "bidirectional"))
      (node (ref "DARROW") (pin "LED-") (pinfunction "LED-_LED-") (pintype "bidirectional"))
      (node (ref "IC2") (pin "11") (pinfunction "DIG1_11") (pintype "output"))
      (node (ref "L") (pin "LED-") (pinfunction "LED-_LED-") (pintype "bidirectional"))
      (node (ref "NUM7") (pin "LED-") (pinfunction "LED-_LED-") (pintype "bidirectional"))
      (node (ref "NUMLK") (pin "LED-") (pinfunction "LED-_LED-") (pintype "bidirectional"))
      (node (ref "O") (pin "LED-") (pinfunction "LED-_LED-") (pintype "bidirectional"))
    )
    (net (code "86") (name "Net-(IC2-DIG2)") (class "Default")
      (node (ref "/") (pin "LED-") (pinfunction "LED-_LED-") (pintype "bidirectional"))
      (node (ref "IC2") (pin "6") (pinfunction "DIG2_6") (pintype "output"))
      (node (ref "NUM/") (pin "LED-") (pinfunction "LED-_LED-") (pintype "bidirectional"))
      (node (ref "NUM8") (pin "LED-") (pinfunction "LED-_LED-") (pintype "bidirectional"))
      (node (ref "P") (pin "LED-") (pinfunction "LED-_LED-") (pintype "bidirectional"))
      (node (ref "RARROW") (pin "LED-") (pinfunction "LED-_LED-") (pintype "bidirectional"))
      (node (ref "SCOLON") (pin "LED-") (pinfunction "LED-_LED-") (pintype "bidirectional"))
    )
    (net (code "87") (name "Net-(IC2-DIG3)") (class "Default")
      (node (ref "'") (pin "LED-") (pinfunction "LED-_LED-") (pintype "bidirectional"))
      (node (ref "IC2") (pin "7") (pinfunction "DIG3_7") (pintype "output"))
      (node (ref "NUM*") (pin "LED-") (pinfunction "LED-_LED-") (pintype "bidirectional"))
      (node (ref "NUM0") (pin "LED-") (pinfunction "LED-_LED-") (pintype "bidirectional"))
      (node (ref "NUM9") (pin "LED-") (pinfunction "LED-_LED-") (pintype "bidirectional"))
      (node (ref "RSHIFT") (pin "LED-") (pinfunction "LED-_LED-") (pintype "bidirectional"))
      (node (ref "[") (pin "LED-") (pinfunction "LED-_LED-") (pintype "bidirectional"))
    )
    (net (code "88") (name "Net-(IC2-DIG4)") (class "Default")
      (node (ref "ENTER") (pin "LED-") (pinfunction "LED-_LED-") (pintype "bidirectional"))
      (node (ref "IC2") (pin "3") (pinfunction "DIG4_3") (pintype "output"))
      (node (ref "NUM+") (pin "LED-") (pinfunction "LED-_LED-") (pintype "bidirectional"))
      (node (ref "NUM-") (pin "LED-") (pinfunction "LED-_LED-") (pintype "bidirectional"))
      (node (ref "NUMENTER") (pin "LED-") (pinfunction "LED-_LED-") (pintype "bidirectional"))
      (node (ref "UARROW") (pin "LED-") (pinfunction "LED-_LED-") (pintype "bidirectional"))
      (node (ref "]") (pin "LED-") (pinfunction "LED-_LED-") (pintype "bidirectional"))
    )
    (net (code "89") (name "Net-(IC2-DIG5)") (class "Default")
      (node (ref "IC2") (pin "10") (pinfunction "DIG5_10") (pintype "output"))
      (node (ref "NUM.") (pin "LED-") (pinfunction "LED-_LED-") (pintype "bidirectional"))
      (node (ref "NUM1") (pin "LED-") (pinfunction "LED-_LED-") (pintype "bidirectional"))
      (node (ref "NUM4") (pin "LED-") (pinfunction "LED-_LED-") (pintype "bidirectional"))
      (node (ref "\\\\") (pin "LED-") (pinfunction "LED-_LED-") (pintype "bidirectional"))
    )
    (net (code "90") (name "Net-(IC2-DIG6)") (class "Default")
      (node (ref "DELETE") (pin "LED-") (pinfunction "LED-_LED-") (pintype "bidirectional"))
      (node (ref "IC2") (pin "5") (pinfunction "DIG6_5") (pintype "output"))
      (node (ref "NUM2") (pin "LED-") (pinfunction "LED-_LED-") (pintype "bidirectional"))
      (node (ref "NUM5") (pin "LED-") (pinfunction "LED-_LED-") (pintype "bidirectional"))
    )
    (net (code "91") (name "Net-(IC2-DIG7)") (class "Default")
      (node (ref "END") (pin "LED-") (pinfunction "LED-_LED-") (pintype "bidirectional"))
      (node (ref "IC2") (pin "8") (pinfunction "DIG7_8") (pintype "output"))
      (node (ref "NUM3") (pin "LED-") (pinfunction "LED-_LED-") (pintype "bidirectional"))
      (node (ref "NUM6") (pin "LED-") (pinfunction "LED-_LED-") (pintype "bidirectional"))
    )
    (net (code "92") (name "Net-(IC2-DIN)") (class "Default")
      (node (ref "IC2") (pin "1") (pinfunction "DIN_1") (pintype "input"))
      (node (ref "U$1") (pin "B2") (pinfunction "_B2_B2") (pintype "bidirectional"))
    )
    (net (code "93") (name "Net-(IC2-ISET)") (class "Default")
      (node (ref "IC2") (pin "18") (pinfunction "ISET_18") (pintype "input"))
      (node (ref "R5") (pin "2") (pinfunction "2_2") (pintype "passive"))
    )
    (net (code "94") (name "Net-(IC2-SEGA)") (class "Default")
      (node (ref "DELETE") (pin "LED+") (pinfunction "LED+_LED+") (pintype "bidirectional"))
      (node (ref "END") (pin "LED+") (pinfunction "LED+_LED+") (pintype "bidirectional"))
      (node (ref "I") (pin "LED+") (pinfunction "LED+_LED+") (pintype "bidirectional"))
      (node (ref "IC2") (pin "14") (pinfunction "SEGA_14") (pintype "output"))
      (node (ref "O") (pin "LED+") (pinfunction "LED+_LED+") (pintype "bidirectional"))
      (node (ref "P") (pin "LED+") (pinfunction "LED+_LED+") (pintype "bidirectional"))
      (node (ref "[") (pin "LED+") (pinfunction "LED+_LED+") (pintype "bidirectional"))
      (node (ref "\\\\") (pin "LED+") (pinfunction "LED+_LED+") (pintype "bidirectional"))
      (node (ref "]") (pin "LED+") (pinfunction "LED+_LED+") (pintype "bidirectional"))
    )
    (net (code "95") (name "Net-(IC2-SEGB)") (class "Default")
      (node (ref "'") (pin "LED+") (pinfunction "LED+_LED+") (pintype "bidirectional"))
      (node (ref "ENTER") (pin "LED+") (pinfunction "LED+_LED+") (pintype "bidirectional"))
      (node (ref "IC2") (pin "16") (pinfunction "SEGB_16") (pintype "output"))
      (node (ref "K") (pin "LED+") (pinfunction "LED+_LED+") (pintype "bidirectional"))
      (node (ref "L") (pin "LED+") (pinfunction "LED+_LED+") (pintype "bidirectional"))
      (node (ref "NUM4") (pin "LED+") (pinfunction "LED+_LED+") (pintype "bidirectional"))
      (node (ref "NUM5") (pin "LED+") (pinfunction "LED+_LED+") (pintype "bidirectional"))
      (node (ref "NUM6") (pin "LED+") (pinfunction "LED+_LED+") (pintype "bidirectional"))
      (node (ref "SCOLON") (pin "LED+") (pinfunction "LED+_LED+") (pintype "bidirectional"))
    )
    (net (code "96") (name "Net-(IC2-SEGC)") (class "Default")
      (node (ref ",") (pin "LED+") (pinfunction "LED+_LED+") (pintype "bidirectional"))
      (node (ref ".") (pin "LED+") (pinfunction "LED+_LED+") (pintype "bidirectional"))
      (node (ref "/") (pin "LED+") (pinfunction "LED+_LED+") (pintype "bidirectional"))
      (node (ref "IC2") (pin "20") (pinfunction "SEGC_20") (pintype "output"))
      (node (ref "NUM1") (pin "LED+") (pinfunction "LED+_LED+") (pintype "bidirectional"))
      (node (ref "NUM2") (pin "LED+") (pinfunction "LED+_LED+") (pintype "bidirectional"))
      (node (ref "NUM3") (pin "LED+") (pinfunction "LED+_LED+") (pintype "bidirectional"))
      (node (ref "RSHIFT") (pin "LED+") (pinfunction "LED+_LED+") (pintype "bidirectional"))
      (node (ref "UARROW") (pin "LED+") (pinfunction "LED+_LED+") (pintype "bidirectional"))
    )
    (net (code "97") (name "Net-(IC2-SEGD)") (class "Default")
      (node (ref "IC2") (pin "23") (pinfunction "SEGD_23") (pintype "output"))
      (node (ref "NUM*") (pin "LED+") (pinfunction "LED+_LED+") (pintype "bidirectional"))
      (node (ref "NUM-") (pin "LED+") (pinfunction "LED+_LED+") (pintype "bidirectional"))
      (node (ref "NUM.") (pin "LED+") (pinfunction "LED+_LED+") (pintype "bidirectional"))
      (node (ref "NUM/") (pin "LED+") (pinfunction "LED+_LED+") (pintype "bidirectional"))
      (node (ref "NUMLK") (pin "LED+") (pinfunction "LED+_LED+") (pintype "bidirectional"))
      (node (ref "PGUP\\") (pin "LED+") (pinfunction "LED+_LED+") (pintype "bidirectional"))
    )
    (net (code "98") (name "Net-(IC2-SEGE)") (class "Default")
      (node (ref "IC2") (pin "21") (pinfunction "SEGE_21") (pintype "output"))
      (node (ref "NUM+") (pin "LED+") (pinfunction "LED+_LED+") (pintype "bidirectional"))
      (node (ref "NUM7") (pin "LED+") (pinfunction "LED+_LED+") (pintype "bidirectional"))
      (node (ref "NUM8") (pin "LED+") (pinfunction "LED+_LED+") (pintype "bidirectional"))
      (node (ref "NUM9") (pin "LED+") (pinfunction "LED+_LED+") (pintype "bidirectional"))
      (node (ref "PGDN") (pin "LED+") (pinfunction "LED+_LED+") (pintype "bidirectional"))
    )
    (net (code "99") (name "Net-(IC2-SEGF)") (class "Default")
      (node (ref "DARROW") (pin "LED+") (pinfunction "LED+_LED+") (pintype "bidirectional"))
      (node (ref "IC2") (pin "15") (pinfunction "SEGF_15") (pintype "output"))
      (node (ref "LARROW") (pin "LED+") (pinfunction "LED+_LED+") (pintype "bidirectional"))
      (node (ref "NUM0") (pin "LED+") (pinfunction "LED+_LED+") (pintype "bidirectional"))
      (node (ref "NUMENTER") (pin "LED+") (pinfunction "LED+_LED+") (pintype "bidirectional"))
      (node (ref "RARROW") (pin "LED+") (pinfunction "LED+_LED+") (pintype "bidirectional"))
    )
    (net (code "100") (name "Net-(INS-P0)") (class "Default")
      (node (ref "D114") (pin "A") (pinfunction "A_A") (pintype "passive"))
      (node (ref "INS") (pin "MX1") (pinfunction "P0_MX1") (pintype "bidirectional"))
    )
    (net (code "101") (name "Net-(J-P0)") (class "Default")
      (node (ref "D307") (pin "A") (pinfunction "A_A") (pintype "passive"))
      (node (ref "J") (pin "MX1") (pinfunction "P0_MX1") (pintype "bidirectional"))
    )
    (net (code "102") (name "Net-(K-P0)") (class "Default")
      (node (ref "D308") (pin "A") (pinfunction "A_A") (pintype "passive"))
      (node (ref "K") (pin "MX1") (pinfunction "P0_MX1") (pintype "bidirectional"))
    )
    (net (code "103") (name "Net-(L-P0)") (class "Default")
      (node (ref "D309") (pin "A") (pinfunction "A_A") (pintype "passive"))
      (node (ref "L") (pin "MX1") (pinfunction "P0_MX1") (pintype "bidirectional"))
    )
    (net (code "104") (name "Net-(LALT-P0)") (class "Default")
      (node (ref "D502") (pin "A") (pinfunction "A_A") (pintype "passive"))
      (node (ref "LALT") (pin "MX1") (pinfunction "P0_MX1") (pintype "bidirectional"))
    )
    (net (code "105") (name "Net-(LARROW-P0)") (class "Default")
      (node (ref "D514") (pin "A") (pinfunction "A_A") (pintype "passive"))
      (node (ref "LARROW") (pin "MX1") (pinfunction "P0_MX1") (pintype "bidirectional"))
    )
    (net (code "106") (name "Net-(LCTRL-P0)") (class "Default")
      (node (ref "D500") (pin "A") (pinfunction "A_A") (pintype "passive"))
      (node (ref "LCTRL") (pin "MX1") (pinfunction "P0_MX1") (pintype "bidirectional"))
    )
    (net (code "107") (name "Net-(LSHIFT-P0)") (class "Default")
      (node (ref "D400") (pin "A") (pinfunction "A_A") (pintype "passive"))
      (node (ref "LSHIFT") (pin "MX1") (pinfunction "P0_MX1") (pintype "bidirectional"))
    )
    (net (code "108") (name "Net-(M-P0)") (class "Default")
      (node (ref "D407") (pin "A") (pinfunction "A_A") (pintype "passive"))
      (node (ref "M") (pin "MX1") (pinfunction "P0_MX1") (pintype "bidirectional"))
    )
    (net (code "109") (name "Net-(MENU-P0)") (class "Default")
      (node (ref "D512") (pin "A") (pinfunction "A_A") (pintype "passive"))
      (node (ref "MENU") (pin "MX1") (pinfunction "P0_MX1") (pintype "bidirectional"))
    )
    (net (code "110") (name "Net-(N-P0)") (class "Default")
      (node (ref "D406") (pin "A") (pinfunction "A_A") (pintype "passive"))
      (node (ref "N") (pin "MX1") (pinfunction "P0_MX1") (pintype "bidirectional"))
    )
    (net (code "111") (name "Net-(NUM*-P0)") (class "Default")
      (node (ref "D119") (pin "A") (pinfunction "A_A") (pintype "passive"))
      (node (ref "NUM*") (pin "MX1") (pinfunction "P0_MX1") (pintype "bidirectional"))
    )
    (net (code "112") (name "Net-(NUM*-P1)") (class "Default")
      (node (ref "NUM*") (pin "MX2") (pinfunction "P1_MX2") (pintype "bidirectional"))
      (node (ref "NUM.") (pin "MX2") (pinfunction "P1_MX2") (pintype "bidirectional"))
      (node (ref "NUM3") (pin "MX2") (pinfunction "P1_MX2") (pintype "bidirectional"))
      (node (ref "NUM6") (pin "MX2") (pinfunction "P1_MX2") (pintype "bidirectional"))
      (node (ref "NUM9") (pin "MX2") (pinfunction "P1_MX2") (pintype "bidirectional"))
      (node (ref "U$1") (pin "C6") (pinfunction "_C6_C6") (pintype "bidirectional"))
    )
    (net (code "113") (name "Net-(NUM+-P0)") (class "Default")
      (node (ref "D220") (pin "A") (pinfunction "A_A") (pintype "passive"))
      (node (ref "NUM+") (pin "MX1") (pinfunction "P0_MX1") (pintype "bidirectional"))
    )
    (net (code "114") (name "Net-(NUM+-P1)") (class "Default")
      (node (ref "NUM+") (pin "MX2") (pinfunction "P1_MX2") (pintype "bidirectional"))
      (node (ref "NUM-") (pin "MX2") (pinfunction "P1_MX2") (pintype "bidirectional"))
      (node (ref "NUMENTER") (pin "MX2") (pinfunction "P1_MX2") (pintype "bidirectional"))
      (node (ref "U$1") (pin "C7") (pinfunction "_C7_C7") (pintype "bidirectional"))
    )
    (net (code "115") (name "Net-(NUM--P0)") (class "Default")
      (node (ref "D120") (pin "A") (pinfunction "A_A") (pintype "passive"))
      (node (ref "NUM-") (pin "MX1") (pinfunction "P0_MX1") (pintype "bidirectional"))
    )
    (net (code "116") (name "Net-(NUM-LED-C)") (class "Default")
      (node (ref "NUM-LED") (pin "K") (pinfunction "C_K") (pintype "passive"))
      (node (ref "R3") (pin "2") (pinfunction "2_2") (pintype "passive"))
    )
    (net (code "117") (name "Net-(NUM.-P0)") (class "Default")
      (node (ref "D519") (pin "A") (pinfunction "A_A") (pintype "passive"))
      (node (ref "NUM.") (pin "MX1") (pinfunction "P0_MX1") (pintype "bidirectional"))
    )
    (net (code "118") (name "Net-(NUM/-P0)") (class "Default")
      (node (ref "D118") (pin "A") (pinfunction "A_A") (pintype "passive"))
      (node (ref "NUM/") (pin "MX1") (pinfunction "P0_MX1") (pintype "bidirectional"))
    )
    (net (code "119") (name "Net-(NUM/-P1)") (class "Default")
      (node (ref "NUM/") (pin "MX2") (pinfunction "P1_MX2") (pintype "bidirectional"))
      (node (ref "NUM2") (pin "MX2") (pinfunction "P1_MX2") (pintype "bidirectional"))
      (node (ref "NUM5") (pin "MX2") (pinfunction "P1_MX2") (pintype "bidirectional"))
      (node (ref "NUM8") (pin "MX2") (pinfunction "P1_MX2") (pintype "bidirectional"))
      (node (ref "U$1") (pin "C5") (pinfunction "_C5_C5") (pintype "bidirectional"))
    )
    (net (code "120") (name "Net-(NUM0-P0)") (class "Default")
      (node (ref "D517") (pin "A") (pinfunction "A_A") (pintype "passive"))
      (node (ref "NUM0") (pin "MX1") (pinfunction "P0_MX1") (pintype "bidirectional"))
    )
    (net (code "121") (name "Net-(NUM0-P1)") (class "Default")
      (node (ref "NUM0") (pin "MX2") (pinfunction "P1_MX2") (pintype "bidirectional"))
      (node (ref "NUM1") (pin "MX2") (pinfunction "P1_MX2") (pintype "bidirectional"))
      (node (ref "NUM4") (pin "MX2") (pinfunction "P1_MX2") (pintype "bidirectional"))
      (node (ref "NUM7") (pin "MX2") (pinfunction "P1_MX2") (pintype "bidirectional"))
      (node (ref "NUMLK") (pin "MX2") (pinfunction "P1_MX2") (pintype "bidirectional"))
      (node (ref "U$1") (pin "C4") (pinfunction "_C4_C4") (pintype "bidirectional"))
    )
    (net (code "122") (name "Net-(NUM1-P0)") (class "Default")
      (node (ref "D417") (pin "A") (pinfunction "A_A") (pintype "passive"))
      (node (ref "NUM1") (pin "MX1") (pinfunction "P0_MX1") (pintype "bidirectional"))
    )
    (net (code "123") (name "Net-(NUM2-P0)") (class "Default")
      (node (ref "D418") (pin "A") (pinfunction "A_A") (pintype "passive"))
      (node (ref "NUM2") (pin "MX1") (pinfunction "P0_MX1") (pintype "bidirectional"))
    )
    (net (code "124") (name "Net-(NUM3-P0)") (class "Default")
      (node (ref "D419") (pin "A") (pinfunction "A_A") (pintype "passive"))
      (node (ref "NUM3") (pin "MX1") (pinfunction "P0_MX1") (pintype "bidirectional"))
    )
    (net (code "125") (name "Net-(NUM4-P0)") (class "Default")
      (node (ref "D317") (pin "A") (pinfunction "A_A") (pintype "passive"))
      (node (ref "NUM4") (pin "MX1") (pinfunction "P0_MX1") (pintype "bidirectional"))
    )
    (net (code "126") (name "Net-(NUM5-P0)") (class "Default")
      (node (ref "D318") (pin "A") (pinfunction "A_A") (pintype "passive"))
      (node (ref "NUM5") (pin "MX1") (pinfunction "P0_MX1") (pintype "bidirectional"))
    )
    (net (code "127") (name "Net-(NUM6-P0)") (class "Default")
      (node (ref "D319") (pin "A") (pinfunction "A_A") (pintype "passive"))
      (node (ref "NUM6") (pin "MX1") (pinfunction "P0_MX1") (pintype "bidirectional"))
    )
    (net (code "128") (name "Net-(NUM7-P0)") (class "Default")
      (node (ref "D217") (pin "A") (pinfunction "A_A") (pintype "passive"))
      (node (ref "NUM7") (pin "MX1") (pinfunction "P0_MX1") (pintype "bidirectional"))
    )
    (net (code "129") (name "Net-(NUM8-P0)") (class "Default")
      (node (ref "D218") (pin "A") (pinfunction "A_A") (pintype "passive"))
      (node (ref "NUM8") (pin "MX1") (pinfunction "P0_MX1") (pintype "bidirectional"))
    )
    (net (code "130") (name "Net-(NUM9-P0)") (class "Default")
      (node (ref "D219") (pin "A") (pinfunction "A_A") (pintype "passive"))
      (node (ref "NUM9") (pin "MX1") (pinfunction "P0_MX1") (pintype "bidirectional"))
    )
    (net (code "131") (name "Net-(NUMENTER-P0)") (class "Default")
      (node (ref "D420") (pin "A") (pinfunction "A_A") (pintype "passive"))
      (node (ref "NUMENTER") (pin "MX1") (pinfunction "P0_MX1") (pintype "bidirectional"))
    )
    (net (code "132") (name "Net-(NUMLK-P0)") (class "Default")
      (node (ref "D117") (pin "A") (pinfunction "A_A") (pintype "passive"))
      (node (ref "NUMLK") (pin "MX1") (pinfunction "P0_MX1") (pintype "bidirectional"))
    )
    (net (code "133") (name "Net-(O-P0)") (class "Default")
      (node (ref "D209") (pin "A") (pinfunction "A_A") (pintype "passive"))
      (node (ref "O") (pin "MX1") (pinfunction "P0_MX1") (pintype "bidirectional"))
    )
    (net (code "134") (name "Net-(P-P0)") (class "Default")
      (node (ref "D210") (pin "A") (pinfunction "A_A") (pintype "passive"))
      (node (ref "P") (pin "MX1") (pinfunction "P0_MX1") (pintype "bidirectional"))
    )
    (net (code "135") (name "Net-(PAUSE-P0)") (class "Default")
      (node (ref "D016") (pin "A") (pinfunction "A_A") (pintype "passive"))
      (node (ref "PAUSE") (pin "MX1") (pinfunction "P0_MX1") (pintype "bidirectional"))
    )
    (net (code "136") (name "Net-(PAUSE-P1)") (class "Default")
      (node (ref "PAUSE") (pin "MX2") (pinfunction "P1_MX2") (pintype "bidirectional"))
      (node (ref "PGDN") (pin "MX2") (pinfunction "P1_MX2") (pintype "bidirectional"))
      (node (ref "PGUP\\") (pin "MX2") (pinfunction "P1_MX2") (pintype "bidirectional"))
      (node (ref "RARROW") (pin "MX2") (pinfunction "P1_MX2") (pintype "bidirectional"))
      (node (ref "U$1") (pin "C3") (pinfunction "_C3_C3") (pintype "bidirectional"))
    )
    (net (code "137") (name "Net-(PGDN-P0)") (class "Default")
      (node (ref "D216") (pin "A") (pinfunction "A_A") (pintype "passive"))
      (node (ref "PGDN") (pin "MX1") (pinfunction "P0_MX1") (pintype "bidirectional"))
    )
    (net (code "138") (name "Net-(PGUP\\-P0)") (class "Default")
      (node (ref "D116") (pin "A") (pinfunction "A_A") (pintype "passive"))
      (node (ref "PGUP\\") (pin "MX1") (pinfunction "P0_MX1") (pintype "bidirectional"))
    )
    (net (code "139") (name "Net-(PRTSC-P0)") (class "Default")
      (node (ref "D014") (pin "A") (pinfunction "A_A") (pintype "passive"))
      (node (ref "PRTSC") (pin "MX1") (pinfunction "P0_MX1") (pintype "bidirectional"))
    )
    (net (code "140") (name "Net-(Q-P0)") (class "Default")
      (node (ref "D201") (pin "A") (pinfunction "A_A") (pintype "passive"))
      (node (ref "Q") (pin "MX1") (pinfunction "P0_MX1") (pintype "bidirectional"))
    )
    (net (code "141") (name "Net-(R-P0)") (class "Default")
      (node (ref "D204") (pin "A") (pinfunction "A_A") (pintype "passive"))
      (node (ref "R") (pin "MX1") (pinfunction "P0_MX1") (pintype "bidirectional"))
    )
    (net (code "142") (name "Net-(RALT-P0)") (class "Default")
      (node (ref "D510") (pin "A") (pinfunction "A_A") (pintype "passive"))
      (node (ref "RALT") (pin "MX1") (pinfunction "P0_MX1") (pintype "bidirectional"))
    )
    (net (code "143") (name "Net-(RARROW-P0)") (class "Default")
      (node (ref "D516") (pin "A") (pinfunction "A_A") (pintype "passive"))
      (node (ref "RARROW") (pin "MX1") (pinfunction "P0_MX1") (pintype "bidirectional"))
    )
    (net (code "144") (name "Net-(RCTRL-P0)") (class "Default")
      (node (ref "D513") (pin "A") (pinfunction "A_A") (pintype "passive"))
      (node (ref "RCTRL") (pin "MX1") (pinfunction "P0_MX1") (pintype "bidirectional"))
    )
    (net (code "145") (name "Net-(RSHIFT-P0)") (class "Default")
      (node (ref "D413") (pin "A") (pinfunction "A_A") (pintype "passive"))
      (node (ref "RSHIFT") (pin "MX1") (pinfunction "P0_MX1") (pintype "bidirectional"))
    )
    (net (code "146") (name "Net-(RWIN-P0)") (class "Default")
      (node (ref "D511") (pin "A") (pinfunction "A_A") (pintype "passive"))
      (node (ref "RWIN") (pin "MX1") (pinfunction "P0_MX1") (pintype "bidirectional"))
    )
    (net (code "147") (name "Net-(S-P0)") (class "Default")
      (node (ref "D302") (pin "A") (pinfunction "A_A") (pintype "passive"))
      (node (ref "S") (pin "MX1") (pinfunction "P0_MX1") (pintype "bidirectional"))
    )
    (net (code "148") (name "Net-(SBAR-P0)") (class "Default")
      (node (ref "D506") (pin "A") (pinfunction "A_A") (pintype "passive"))
      (node (ref "SBAR") (pin "MX1") (pinfunction "P0_MX1") (pintype "bidirectional"))
    )
    (net (code "149") (name "Net-(SCOLON-P0)") (class "Default")
      (node (ref "D310") (pin "A") (pinfunction "A_A") (pintype "passive"))
      (node (ref "SCOLON") (pin "MX1") (pinfunction "P0_MX1") (pintype "bidirectional"))
    )
    (net (code "150") (name "Net-(SCRLOCK-P0)") (class "Default")
      (node (ref "D015") (pin "A") (pinfunction "A_A") (pintype "passive"))
      (node (ref "SCRLOCK") (pin "MX1") (pinfunction "P0_MX1") (pintype "bidirectional"))
    )
    (net (code "151") (name "Net-(SCROLL-LED-C)") (class "Default")
      (node (ref "R1") (pin "2") (pinfunction "2_2") (pintype "passive"))
      (node (ref "SCROLL-LED") (pin "K") (pinfunction "C_K") (pintype "passive"))
    )
    (net (code "152") (name "Net-(T-P0)") (class "Default")
      (node (ref "D205") (pin "A") (pinfunction "A_A") (pintype "passive"))
      (node (ref "T") (pin "MX1") (pinfunction "P0_MX1") (pintype "bidirectional"))
    )
    (net (code "153") (name "Net-(TAB-P0)") (class "Default")
      (node (ref "D200") (pin "A") (pinfunction "A_A") (pintype "passive"))
      (node (ref "TAB") (pin "MX1") (pinfunction "P0_MX1") (pintype "bidirectional"))
    )
    (net (code "154") (name "Net-(U$1-VCC)") (class "Default")
      (node (ref "PWR") (pin "2") (pinfunction "2_2") (pintype "passive"))
      (node (ref "U$1") (pin "5V") (pinfunction "VCC_5V") (pintype "power_in"))
    )
    (net (code "155") (name "Net-(U$1-_A0)") (class "Default")
      (node (ref "SV1") (pin "1") (pinfunction "1_1") (pintype "passive"))
      (node (ref "U$1") (pin "A0") (pinfunction "_A0_A0") (pintype "bidirectional"))
    )
    (net (code "156") (name "Net-(U$1-_A1)") (class "Default")
      (node (ref "SV1") (pin "3") (pinfunction "3_3") (pintype "passive"))
      (node (ref "U$1") (pin "A1") (pinfunction "_A1_A1") (pintype "bidirectional"))
    )
    (net (code "157") (name "Net-(U$1-_A2)") (class "Default")
      (node (ref "SV1") (pin "5") (pinfunction "5_5") (pintype "passive"))
      (node (ref "U$1") (pin "A2") (pinfunction "_A2_A2") (pintype "bidirectional"))
    )
    (net (code "158") (name "Net-(U$1-_A3)") (class "Default")
      (node (ref "SV1") (pin "7") (pinfunction "7_7") (pintype "passive"))
      (node (ref "U$1") (pin "A3") (pinfunction "_A3_A3") (pintype "bidirectional"))
    )
    (net (code "159") (name "Net-(U$1-_A4)") (class "Default")
      (node (ref "SV1") (pin "2") (pinfunction "2_2") (pintype "passive"))
      (node (ref "U$1") (pin "A4") (pinfunction "_A4_A4") (pintype "bidirectional"))
    )
    (net (code "160") (name "Net-(U$1-_A5)") (class "Default")
      (node (ref "SV1") (pin "4") (pinfunction "4_4") (pintype "passive"))
      (node (ref "U$1") (pin "A5") (pinfunction "_A5_A5") (pintype "bidirectional"))
    )
    (net (code "161") (name "Net-(U$1-_A6)") (class "Default")
      (node (ref "SV1") (pin "6") (pinfunction "6_6") (pintype "passive"))
      (node (ref "U$1") (pin "A6") (pinfunction "_A6_A6") (pintype "bidirectional"))
    )
    (net (code "162") (name "Net-(U$1-_A7)") (class "Default")
      (node (ref "SV1") (pin "8") (pinfunction "8_8") (pintype "passive"))
      (node (ref "U$1") (pin "A7") (pinfunction "_A7_A7") (pintype "bidirectional"))
    )
    (net (code "163") (name "Net-(U$1-_E6)") (class "Default")
      (node (ref "D500") (pin "C") (pinfunction "C_C") (pintype "passive"))
      (node (ref "D501") (pin "C") (pinfunction "C_C") (pintype "passive"))
      (node (ref "D502") (pin "C") (pinfunction "C_C") (pintype "passive"))
      (node (ref "D506") (pin "C") (pinfunction "C_C") (pintype "passive"))
      (node (ref "D510") (pin "C") (pinfunction "C_C") (pintype "passive"))
      (node (ref "D511") (pin "C") (pinfunction "C_C") (pintype "passive"))
      (node (ref "D512") (pin "C") (pinfunction "C_C") (pintype "passive"))
      (node (ref "D513") (pin "C") (pinfunction "C_C") (pintype "passive"))
      (node (ref "D514") (pin "C") (pinfunction "C_C") (pintype "passive"))
      (node (ref "D515") (pin "C") (pinfunction "C_C") (pintype "passive"))
      (node (ref "D516") (pin "C") (pinfunction "C_C") (pintype "passive"))
      (node (ref "D517") (pin "C") (pinfunction "C_C") (pintype "passive"))
      (node (ref "D519") (pin "C") (pinfunction "C_C") (pintype "passive"))
      (node (ref "U$1") (pin "E6") (pinfunction "_E6_E6") (pintype "bidirectional"))
    )
    (net (code "164") (name "Net-(U$1-_F0)") (class "Default")
      (node (ref "D400") (pin "C") (pinfunction "C_C") (pintype "passive"))
      (node (ref "D401") (pin "C") (pinfunction "C_C") (pintype "passive"))
      (node (ref "D402") (pin "C") (pinfunction "C_C") (pintype "passive"))
      (node (ref "D403") (pin "C") (pinfunction "C_C") (pintype "passive"))
      (node (ref "D404") (pin "C") (pinfunction "C_C") (pintype "passive"))
      (node (ref "D405") (pin "C") (pinfunction "C_C") (pintype "passive"))
      (node (ref "D406") (pin "C") (pinfunction "C_C") (pintype "passive"))
      (node (ref "D407") (pin "C") (pinfunction "C_C") (pintype "passive"))
      (node (ref "D408") (pin "C") (pinfunction "C_C") (pintype "passive"))
      (node (ref "D409") (pin "C") (pinfunction "C_C") (pintype "passive"))
      (node (ref "D410") (pin "C") (pinfunction "C_C") (pintype "passive"))
      (node (ref "D413") (pin "C") (pinfunction "C_C") (pintype "passive"))
      (node (ref "D415") (pin "C") (pinfunction "C_C") (pintype "passive"))
      (node (ref "D417") (pin "C") (pinfunction "C_C") (pintype "passive"))
      (node (ref "D418") (pin "C") (pinfunction "C_C") (pintype "passive"))
      (node (ref "D419") (pin "C") (pinfunction "C_C") (pintype "passive"))
      (node (ref "D420") (pin "C") (pinfunction "C_C") (pintype "passive"))
      (node (ref "U$1") (pin "F0") (pinfunction "_F0_F0") (pintype "bidirectional"))
    )
    (net (code "165") (name "Net-(U$1-_F1)") (class "Default")
      (node (ref "D300") (pin "C") (pinfunction "C_C") (pintype "passive"))
      (node (ref "D301") (pin "C") (pinfunction "C_C") (pintype "passive"))
      (node (ref "D302") (pin "C") (pinfunction "C_C") (pintype "passive"))
      (node (ref "D303") (pin "C") (pinfunction "C_C") (pintype "passive"))
      (node (ref "D304") (pin "C") (pinfunction "C_C") (pintype "passive"))
      (node (ref "D305") (pin "C") (pinfunction "C_C") (pintype "passive"))
      (node (ref "D306") (pin "C") (pinfunction "C_C") (pintype "passive"))
      (node (ref "D307") (pin "C") (pinfunction "C_C") (pintype "passive"))
      (node (ref "D308") (pin "C") (pinfunction "C_C") (pintype "passive"))
      (node (ref "D309") (pin "C") (pinfunction "C_C") (pintype "passive"))
      (node (ref "D310") (pin "C") (pinfunction "C_C") (pintype "passive"))
      (node (ref "D311") (pin "C") (pinfunction "C_C") (pintype "passive"))
      (node (ref "D313") (pin "C") (pinfunction "C_C") (pintype "passive"))
      (node (ref "D317") (pin "C") (pinfunction "C_C") (pintype "passive"))
      (node (ref "D318") (pin "C") (pinfunction "C_C") (pintype "passive"))
      (node (ref "D319") (pin "C") (pinfunction "C_C") (pintype "passive"))
      (node (ref "U$1") (pin "F1") (pinfunction "_F1_F1") (pintype "bidirectional"))
    )
    (net (code "166") (name "Net-(U$1-_F2)") (class "Default")
      (node (ref "D200") (pin "C") (pinfunction "C_C") (pintype "passive"))
      (node (ref "D201") (pin "C") (pinfunction "C_C") (pintype "passive"))
      (node (ref "D202") (pin "C") (pinfunction "C_C") (pintype "passive"))
      (node (ref "D203") (pin "C") (pinfunction "C_C") (pintype "passive"))
      (node (ref "D204") (pin "C") (pinfunction "C_C") (pintype "passive"))
      (node (ref "D205") (pin "C") (pinfunction "C_C") (pintype "passive"))
      (node (ref "D206") (pin "C") (pinfunction "C_C") (pintype "passive"))
      (node (ref "D207") (pin "C") (pinfunction "C_C") (pintype "passive"))
      (node (ref "D208") (pin "C") (pinfunction "C_C") (pintype "passive"))
      (node (ref "D209") (pin "C") (pinfunction "C_C") (pintype "passive"))
      (node (ref "D210") (pin "C") (pinfunction "C_C") (pintype "passive"))
      (node (ref "D211") (pin "C") (pinfunction "C_C") (pintype "passive"))
      (node (ref "D212") (pin "C") (pinfunction "C_C") (pintype "passive"))
      (node (ref "D213") (pin "C") (pinfunction "C_C") (pintype "passive"))
      (node (ref "D214") (pin "C") (pinfunction "C_C") (pintype "passive"))
      (node (ref "D215") (pin "C") (pinfunction "C_C") (pintype "passive"))
      (node (ref "D216") (pin "C") (pinfunction "C_C") (pintype "passive"))
      (node (ref "D217") (pin "C") (pinfunction "C_C") (pintype "passive"))
      (node (ref "D218") (pin "C") (pinfunction "C_C") (pintype "passive"))
      (node (ref "D219") (pin "C") (pinfunction "C_C") (pintype "passive"))
      (node (ref "D220") (pin "C") (pinfunction "C_C") (pintype "passive"))
      (node (ref "U$1") (pin "F2") (pinfunction "_F2_F2") (pintype "bidirectional"))
    )
    (net (code "167") (name "Net-(U$1-_F3)") (class "Default")
      (node (ref "D100") (pin "C") (pinfunction "C_C") (pintype "passive"))
      (node (ref "D101") (pin "C") (pinfunction "C_C") (pintype "passive"))
      (node (ref "D102") (pin "C") (pinfunction "C_C") (pintype "passive"))
      (node (ref "D103") (pin "C") (pinfunction "C_C") (pintype "passive"))
      (node (ref "D104") (pin "C") (pinfunction "C_C") (pintype "passive"))
      (node (ref "D105") (pin "C") (pinfunction "C_C") (pintype "passive"))
      (node (ref "D106") (pin "C") (pinfunction "C_C") (pintype "passive"))
      (node (ref "D107") (pin "C") (pinfunction "C_C") (pintype "passive"))
      (node (ref "D108") (pin "C") (pinfunction "C_C") (pintype "passive"))
      (node (ref "D109") (pin "C") (pinfunction "C_C") (pintype "passive"))
      (node (ref "D110") (pin "C") (pinfunction "C_C") (pintype "passive"))
      (node (ref "D111") (pin "C") (pinfunction "C_C") (pintype "passive"))
      (node (ref "D112") (pin "C") (pinfunction "C_C") (pintype "passive"))
      (node (ref "D113") (pin "C") (pinfunction "C_C") (pintype "passive"))
      (node (ref "D114") (pin "C") (pinfunction "C_C") (pintype "passive"))
      (node (ref "D115") (pin "C") (pinfunction "C_C") (pintype "passive"))
      (node (ref "D116") (pin "C") (pinfunction "C_C") (pintype "passive"))
      (node (ref "D117") (pin "C") (pinfunction "C_C") (pintype "passive"))
      (node (ref "D118") (pin "C") (pinfunction "C_C") (pintype "passive"))
      (node (ref "D119") (pin "C") (pinfunction "C_C") (pintype "passive"))
      (node (ref "D120") (pin "C") (pinfunction "C_C") (pintype "passive"))
      (node (ref "U$1") (pin "F3") (pinfunction "_F3_F3") (pintype "bidirectional"))
    )
    (net (code "168") (name "Net-(U$1-_F4)") (class "Default")
      (node (ref "D000") (pin "C") (pinfunction "C_C") (pintype "passive"))
      (node (ref "D001") (pin "C") (pinfunction "C_C") (pintype "passive"))
      (node (ref "D002") (pin "C") (pinfunction "C_C") (pintype "passive"))
      (node (ref "D003") (pin "C") (pinfunction "C_C") (pintype "passive"))
      (node (ref "D004") (pin "C") (pinfunction "C_C") (pintype "passive"))
      (node (ref "D005") (pin "C") (pinfunction "C_C") (pintype "passive"))
      (node (ref "D006") (pin "C") (pinfunction "C_C") (pintype "passive"))
      (node (ref "D007") (pin "C") (pinfunction "C_C") (pintype "passive"))
      (node (ref "D008") (pin "C") (pinfunction "C_C") (pintype "passive"))
      (node (ref "D009") (pin "C") (pinfunction "C_C") (pintype "passive"))
      (node (ref "D010") (pin "C") (pinfunction "C_C") (pintype "passive"))
      (node (ref "D011") (pin "C") (pinfunction "C_C") (pintype "passive"))
      (node (ref "D012") (pin "C") (pinfunction "C_C") (pintype "passive"))
      (node (ref "D014") (pin "C") (pinfunction "C_C") (pintype "passive"))
      (node (ref "D015") (pin "C") (pinfunction "C_C") (pintype "passive"))
      (node (ref "D016") (pin "C") (pinfunction "C_C") (pintype "passive"))
      (node (ref "U$1") (pin "F4") (pinfunction "_F4_F4") (pintype "bidirectional"))
    )
    (net (code "169") (name "Net-(U$1-_F5)") (class "Default")
      (node (ref "SCROLL-LED") (pin "A") (pinfunction "A_A") (pintype "passive"))
      (node (ref "U$1") (pin "F5") (pinfunction "_F5_F5") (pintype "bidirectional"))
    )
    (net (code "170") (name "Net-(U$1-_F6)") (class "Default")
      (node (ref "CAPS-LED") (pin "A") (pinfunction "A_A") (pintype "passive"))
      (node (ref "U$1") (pin "F6") (pinfunction "_F6_F6") (pintype "bidirectional"))
    )
    (net (code "171") (name "Net-(U$1-_F7)") (class "Default")
      (node (ref "NUM-LED") (pin "A") (pinfunction "A_A") (pintype "passive"))
      (node (ref "U$1") (pin "F7") (pinfunction "_F7_F7") (pintype "bidirectional"))
    )
    (net (code "172") (name "Net-(U-P0)") (class "Default")
      (node (ref "D207") (pin "A") (pinfunction "A_A") (pintype "passive"))
      (node (ref "U") (pin "MX1") (pinfunction "P0_MX1") (pintype "bidirectional"))
    )
    (net (code "173") (name "Net-(UARROW-P0)") (class "Default")
      (node (ref "D415") (pin "A") (pinfunction "A_A") (pintype "passive"))
      (node (ref "UARROW") (pin "MX1") (pinfunction "P0_MX1") (pintype "bidirectional"))
    )
    (net (code "174") (name "Net-(V-P0)") (class "Default")
      (node (ref "D404") (pin "A") (pinfunction "A_A") (pintype "passive"))
      (node (ref "V") (pin "MX1") (pinfunction "P0_MX1") (pintype "bidirectional"))
    )
    (net (code "175") (name "Net-(W-P0)") (class "Default")
      (node (ref "D202") (pin "A") (pinfunction "A_A") (pintype "passive"))
      (node (ref "W") (pin "MX1") (pinfunction "P0_MX1") (pintype "bidirectional"))
    )
    (net (code "176") (name "Net-(WIN-P0)") (class "Default")
      (node (ref "D501") (pin "A") (pinfunction "A_A") (pintype "passive"))
      (node (ref "WIN") (pin "MX1") (pinfunction "P0_MX1") (pintype "bidirectional"))
    )
    (net (code "177") (name "Net-(X-P0)") (class "Default")
      (node (ref "D402") (pin "A") (pinfunction "A_A") (pintype "passive"))
      (node (ref "X") (pin "MX1") (pinfunction "P0_MX1") (pintype "bidirectional"))
    )
    (net (code "178") (name "Net-(Y-P0)") (class "Default")
      (node (ref "D206") (pin "A") (pinfunction "A_A") (pintype "passive"))
      (node (ref "Y") (pin "MX1") (pinfunction "P0_MX1") (pintype "bidirectional"))
    )
    (net (code "179") (name "Net-(Z-P0)") (class "Default")
      (node (ref "D401") (pin "A") (pinfunction "A_A") (pintype "passive"))
      (node (ref "Z") (pin "MX1") (pinfunction "P0_MX1") (pintype "bidirectional"))
    )
    (net (code "180") (name "Net-([-P0)") (class "Default")
      (node (ref "D211") (pin "A") (pinfunction "A_A") (pintype "passive"))
      (node (ref "[") (pin "MX1") (pinfunction "P0_MX1") (pintype "bidirectional"))
    )
    (net (code "181") (name "Net-(\\\\-P0)") (class "Default")
      (node (ref "D213") (pin "A") (pinfunction "A_A") (pintype "passive"))
      (node (ref "\\\\") (pin "MX1") (pinfunction "P0_MX1") (pintype "bidirectional"))
    )
    (net (code "182") (name "Net-(]-P0)") (class "Default")
      (node (ref "D212") (pin "A") (pinfunction "A_A") (pintype "passive"))
      (node (ref "]") (pin "MX1") (pinfunction "P0_MX1") (pintype "bidirectional"))
    )
    (net (code "183") (name "Net-(`-P0)") (class "Default")
      (node (ref "D100") (pin "A") (pinfunction "A_A") (pintype "passive"))
      (node (ref "`") (pin "MX1") (pinfunction "P0_MX1") (pintype "bidirectional"))
    )
    (net (code "184") (name "VCC") (class "Default")
      (node (ref "C1") (pin "1") (pinfunction "1_1") (pintype "passive"))
      (node (ref "C2") (pin "1") (pinfunction "1_1") (pintype "passive"))
      (node (ref "IC1") (pin "19") (pinfunction "VCC_19") (pintype "power_in"))
      (node (ref "IC2") (pin "19") (pinfunction "VCC_19") (pintype "power_in"))
      (node (ref "R4") (pin "1") (pinfunction "1_1") (pintype "passive"))
      (node (ref "R5") (pin "1") (pinfunction "1_1") (pintype "passive"))
      (node (ref "U$1") (pin "+5V") (pinfunction "+5V_+5V") (pintype "power_in"))
    )
    (net (code "185") (name "unconnected-(IC1-DOUT-Pad24)") (class "Default")
      (node (ref "IC1") (pin "24") (pinfunction "DOUT_24") (pintype "output"))
    )
    (net (code "186") (name "unconnected-(IC2-SEGDP-Pad22)") (class "Default")
      (node (ref "IC2") (pin "22") (pinfunction "SEGDP_22") (pintype "output"))
    )
    (net (code "187") (name "unconnected-(IC2-SEGG-Pad17)") (class "Default")
      (node (ref "IC2") (pin "17") (pinfunction "SEGG_17") (pintype "output"))
    )
    (net (code "188") (name "unconnected-(U$1-_B3-PadB3)") (class "Default")
      (node (ref "U$1") (pin "B3") (pinfunction "_B3_B3") (pintype "bidirectional"))
    )
    (net (code "189") (name "unconnected-(U$1-_D6-PadD6)") (class "Default")
      (node (ref "U$1") (pin "D6") (pinfunction "_D6_D6") (pintype "bidirectional"))
    )
    (net (code "190") (name "unconnected-(U$1-_E4-PadE4)") (class "Default")
      (node (ref "U$1") (pin "E4") (pinfunction "_E4_E4") (pintype "bidirectional"))
    )
    (net (code "191") (name "unconnected-(U$1-_E5-PadE5)") (class "Default")
      (node (ref "U$1") (pin "E5") (pinfunction "_E5_E5") (pintype "bidirectional"))
    )
    (net (code "192") (name "unconnected-(U$1-_E7-PadE7)") (class "Default")
      (node (ref "U$1") (pin "E7") (pinfunction "_E7_E7") (pintype "bidirectional"))
    )
    (net (code "193") (name "unconnected-(U$1-_REF-PadREF)") (class "Default")
      (node (ref "U$1") (pin "REF") (pinfunction "_REF_REF") (pintype "input"))
    )
    (net (code "194") (name "unconnected-(U$1-_RST-PadRST)") (class "Default")
      (node (ref "U$1") (pin "RST") (pinfunction "_RST_RST") (pintype "input"))
    )
  )
)
